# CubePCB.net
KiCad netlist of a schematic drawn in EAGLE
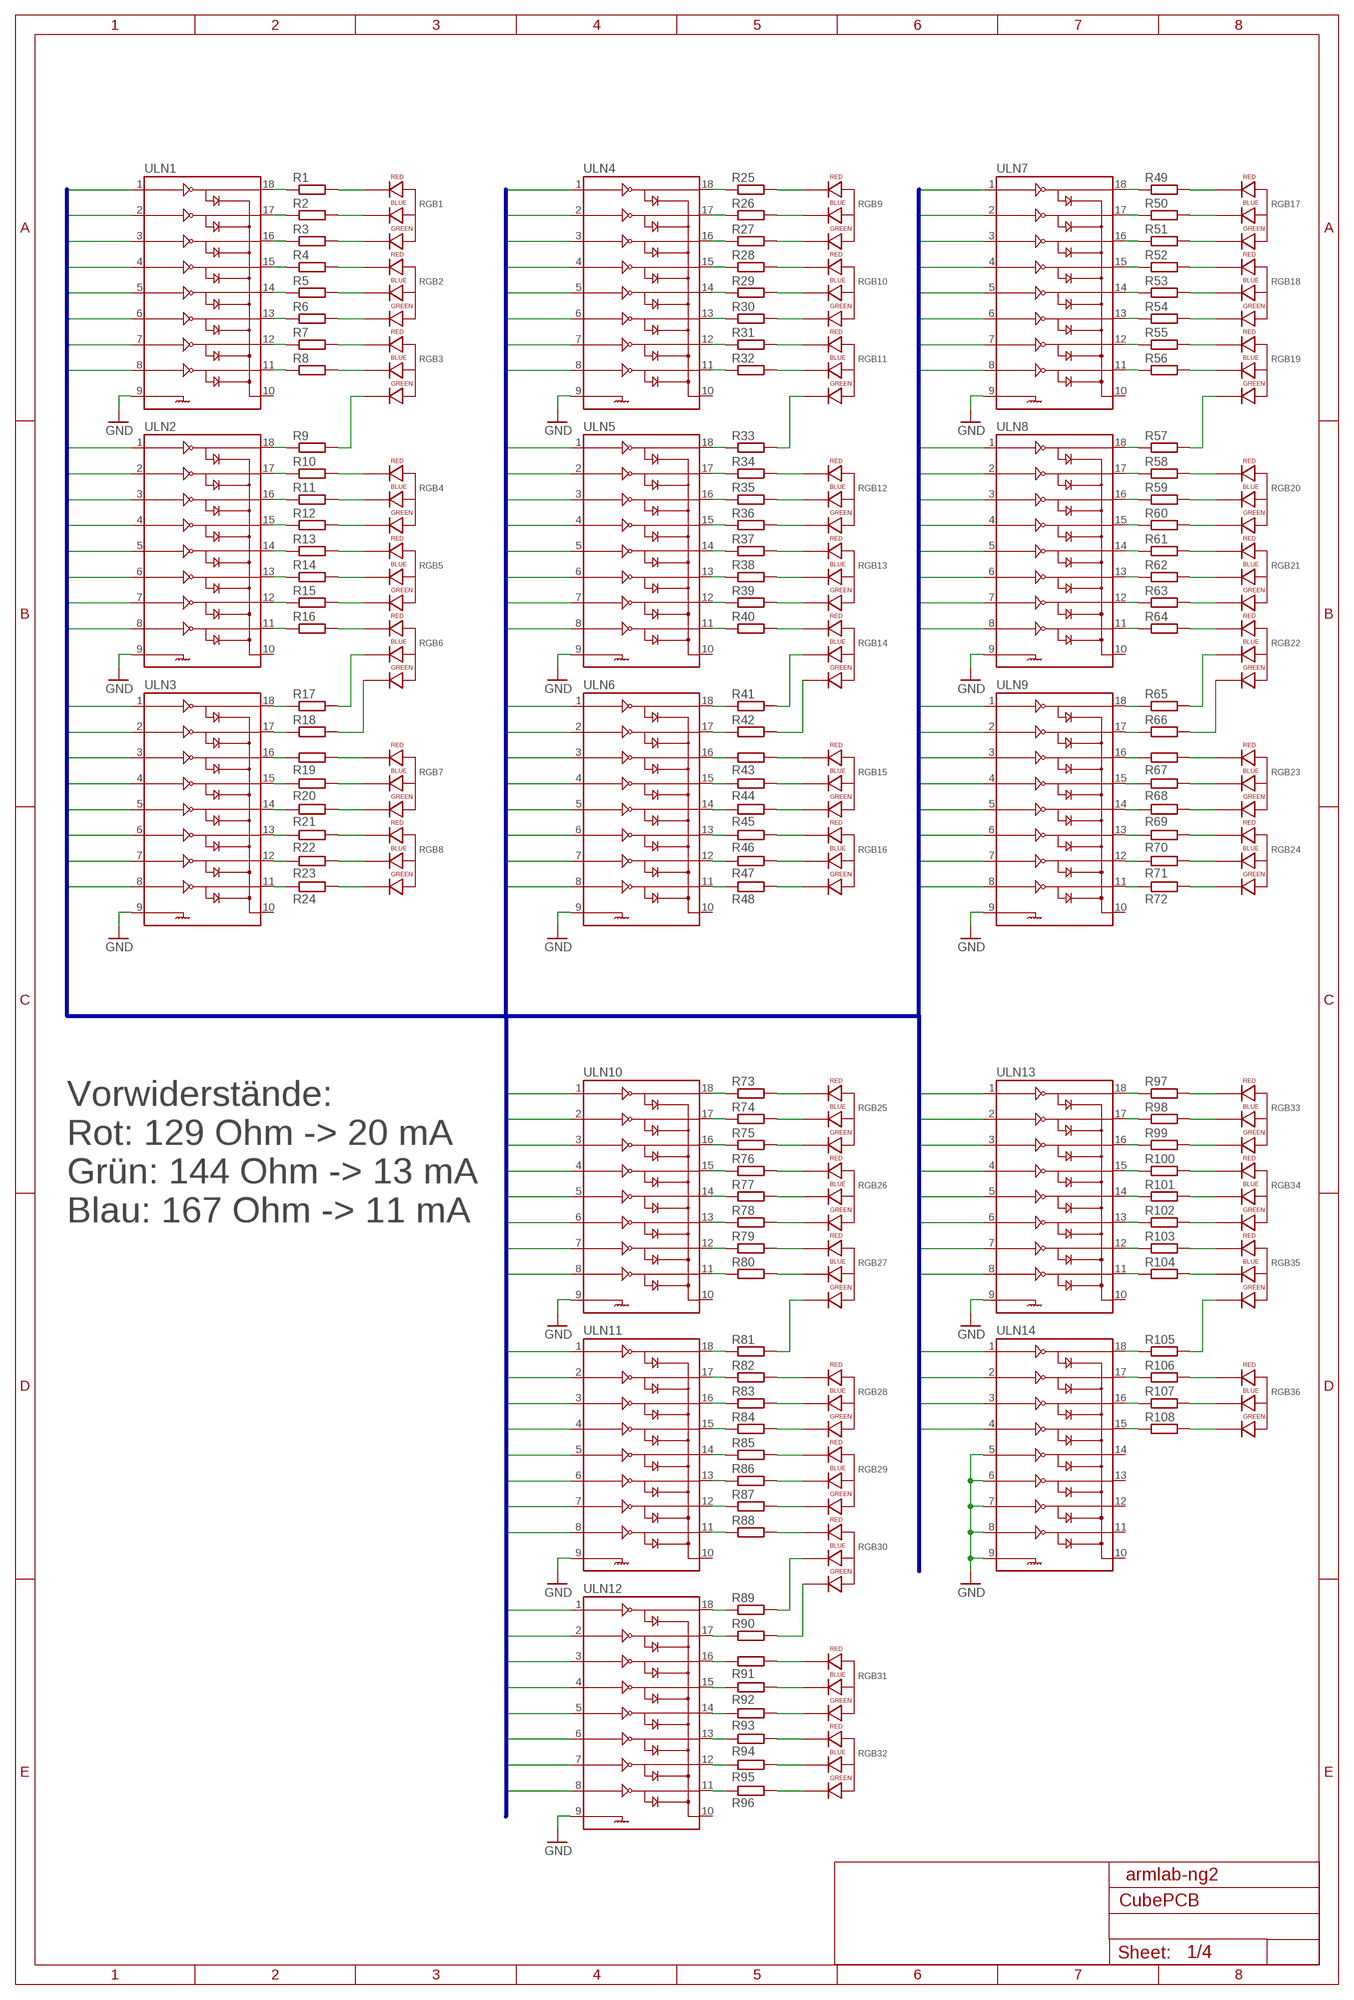
[diagram p0: schematic, sheet 1]
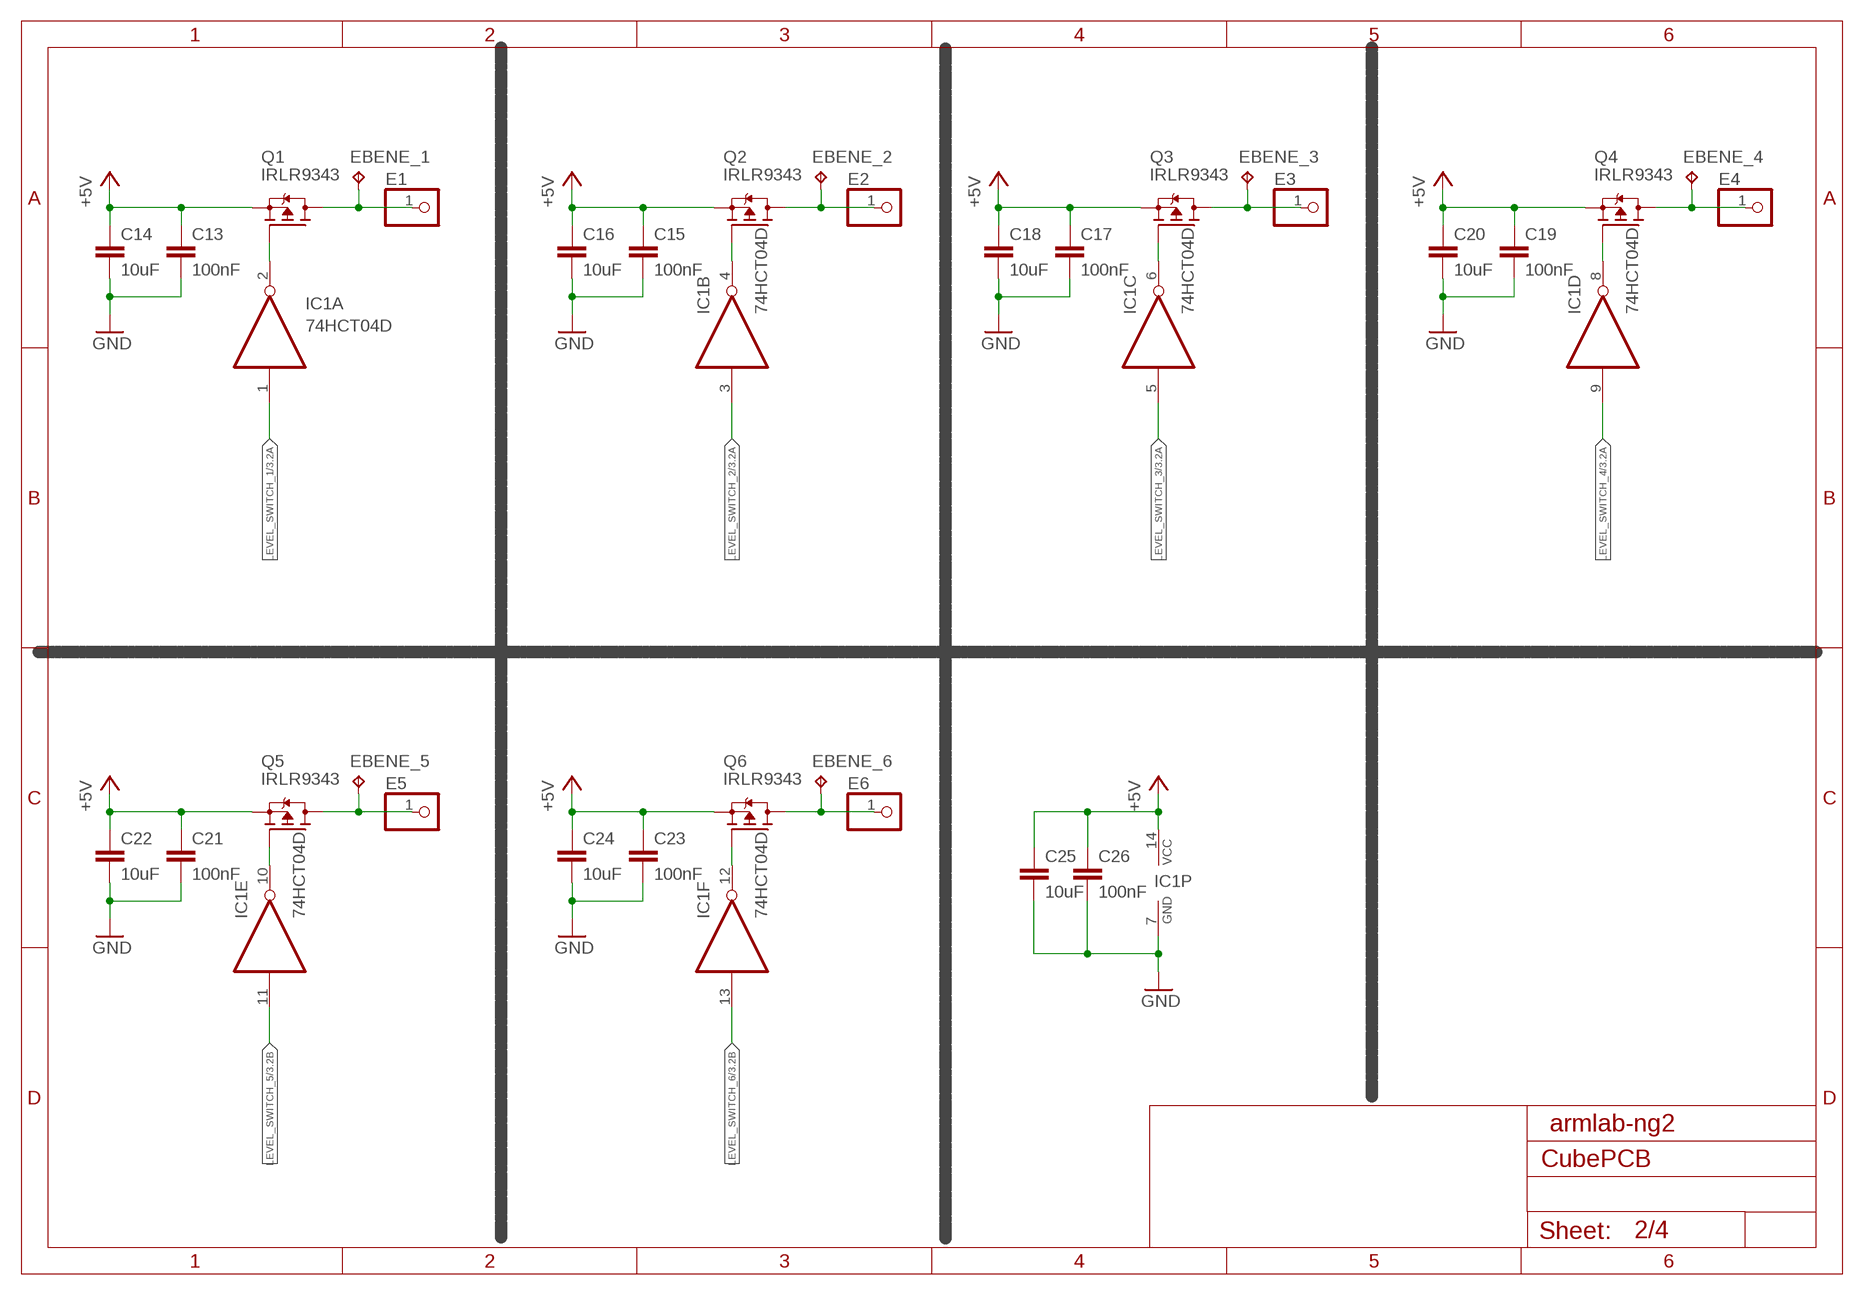
[diagram p1: schematic, sheet 2]
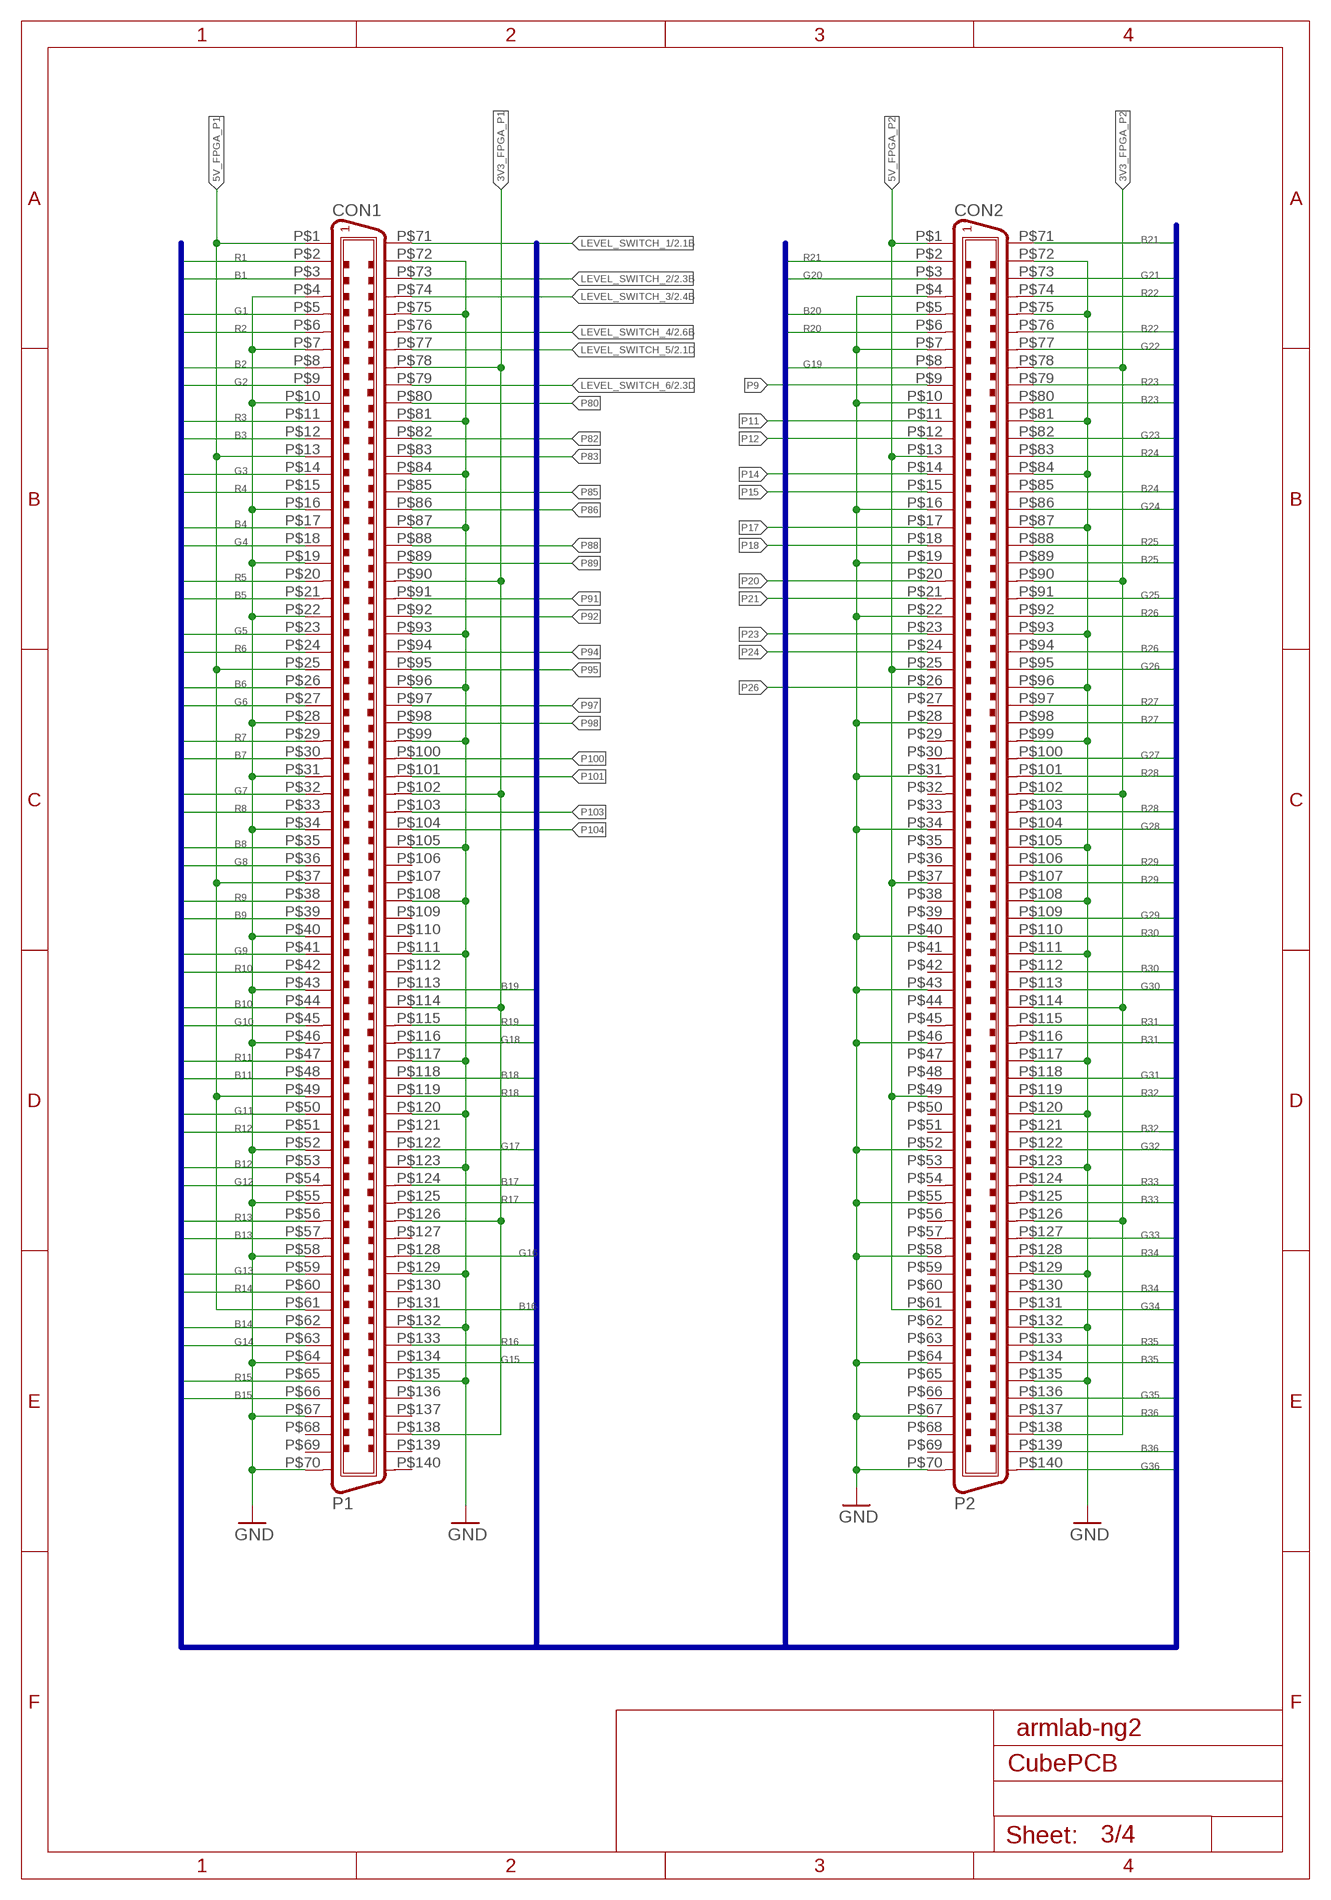
[diagram p2: schematic, sheet 3]
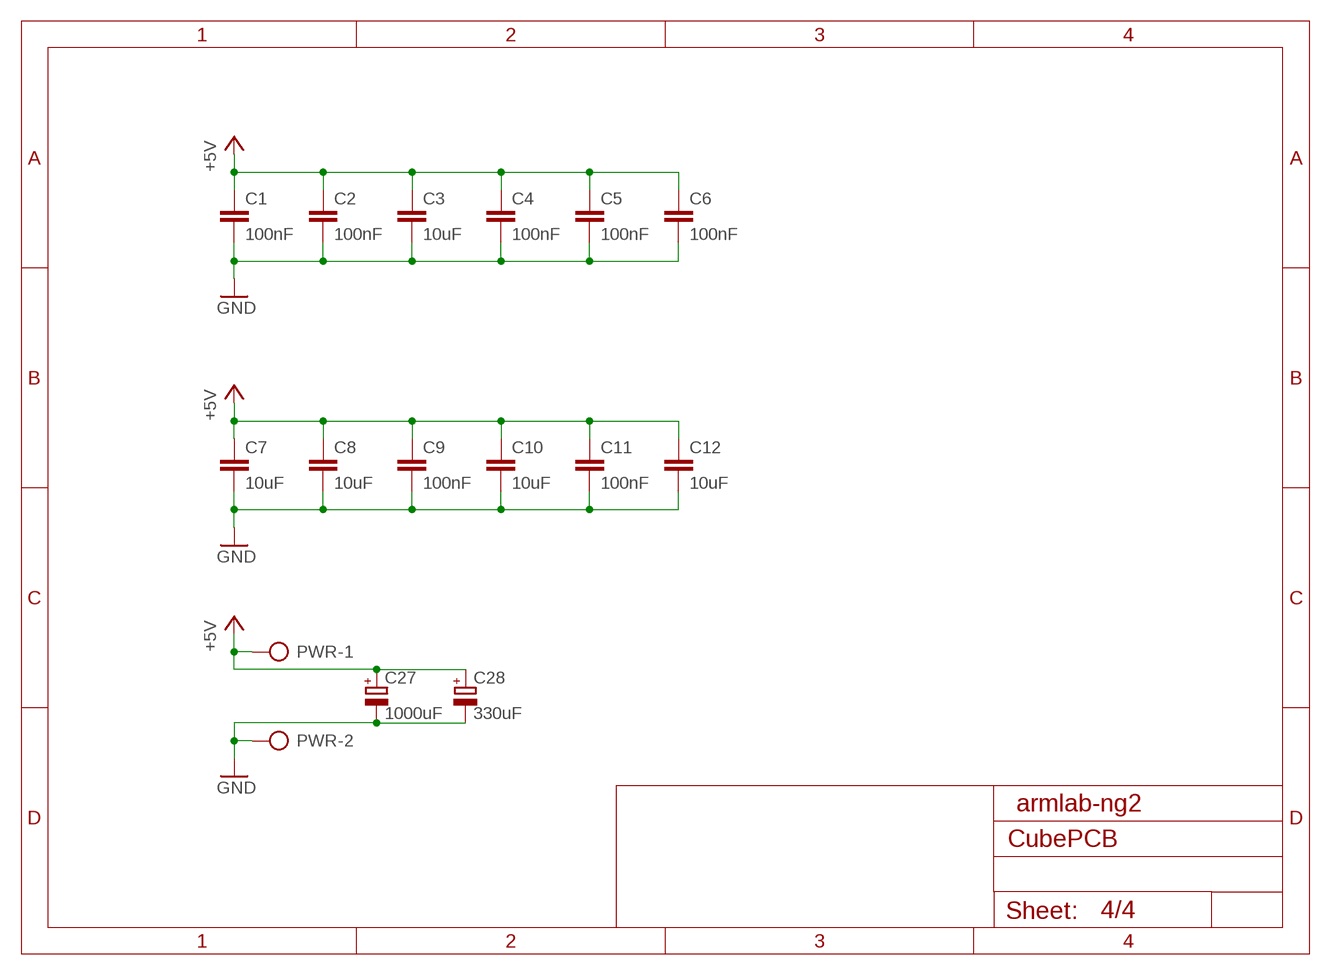
[diagram p3: schematic, sheet 4]

(export (version "E")
  (design (tool "Eeschema 10.0.6"))
  (components
    (comp (ref "C13")
      (value "100nF")
      (footprint "eagle-import:C0603K")
      (libsource (lib "eagle-import") (part "C-EUC0603K"))
    )
    (comp (ref "C14")
      (value "10uF")
      (footprint "eagle-import:C0603K")
      (libsource (lib "eagle-import") (part "C-EUC0603K"))
    )
    (comp (ref "C15")
      (value "100nF")
      (footprint "eagle-import:C0603K")
      (libsource (lib "eagle-import") (part "C-EUC0603K"))
    )
    (comp (ref "C16")
      (value "10uF")
      (footprint "eagle-import:C0603K")
      (libsource (lib "eagle-import") (part "C-EUC0603K"))
    )
    (comp (ref "C17")
      (value "100nF")
      (footprint "eagle-import:C0603K")
      (libsource (lib "eagle-import") (part "C-EUC0603K"))
    )
    (comp (ref "C18")
      (value "10uF")
      (footprint "eagle-import:C0603K")
      (libsource (lib "eagle-import") (part "C-EUC0603K"))
    )
    (comp (ref "C19")
      (value "100nF")
      (footprint "eagle-import:C0603K")
      (libsource (lib "eagle-import") (part "C-EUC0603K"))
    )
    (comp (ref "C20")
      (value "10uF")
      (footprint "eagle-import:C0603K")
      (libsource (lib "eagle-import") (part "C-EUC0603K"))
    )
    (comp (ref "C21")
      (value "100nF")
      (footprint "eagle-import:C0603K")
      (libsource (lib "eagle-import") (part "C-EUC0603K"))
    )
    (comp (ref "C22")
      (value "10uF")
      (footprint "eagle-import:C0603K")
      (libsource (lib "eagle-import") (part "C-EUC0603K"))
    )
    (comp (ref "C23")
      (value "100nF")
      (footprint "eagle-import:C0603K")
      (libsource (lib "eagle-import") (part "C-EUC0603K"))
    )
    (comp (ref "C24")
      (value "10uF")
      (footprint "eagle-import:C0603K")
      (libsource (lib "eagle-import") (part "C-EUC0603K"))
    )
    (comp (ref "C25")
      (value "10uF")
      (footprint "eagle-import:C0603K")
      (libsource (lib "eagle-import") (part "C-EUC0603K"))
    )
    (comp (ref "C26")
      (value "100nF")
      (footprint "eagle-import:C0603K")
      (libsource (lib "eagle-import") (part "C-EUC0603K"))
    )
    (comp (ref "E1")
      (value "PINHD-1X1/LONG")
      (footprint "eagle-import:1X01")
      (libsource (lib "eagle-import") (part "PINHD-1X1/LONG"))
    )
    (comp (ref "E2")
      (value "PINHD-1X1/LONG")
      (footprint "eagle-import:1X01")
      (libsource (lib "eagle-import") (part "PINHD-1X1/LONG"))
    )
    (comp (ref "E3")
      (value "PINHD-1X1/LONG")
      (footprint "eagle-import:1X01")
      (libsource (lib "eagle-import") (part "PINHD-1X1/LONG"))
    )
    (comp (ref "E4")
      (value "PINHD-1X1/LONG")
      (footprint "eagle-import:1X01")
      (libsource (lib "eagle-import") (part "PINHD-1X1/LONG"))
    )
    (comp (ref "E5")
      (value "PINHD-1X1/LONG")
      (footprint "eagle-import:1X01")
      (libsource (lib "eagle-import") (part "PINHD-1X1/LONG"))
    )
    (comp (ref "E6")
      (value "PINHD-1X1/LONG")
      (footprint "eagle-import:1X01")
      (libsource (lib "eagle-import") (part "PINHD-1X1/LONG"))
    )
    (comp (ref "EBENE_1")
      (value "TPB1,27")
      (footprint "eagle-import:B1,27")
      (libsource (lib "eagle-import") (part "TPB1,27"))
    )
    (comp (ref "EBENE_2")
      (value "TPB1,27")
      (footprint "eagle-import:B1,27")
      (libsource (lib "eagle-import") (part "TPB1,27"))
    )
    (comp (ref "EBENE_3")
      (value "TPB1,27")
      (footprint "eagle-import:B1,27")
      (libsource (lib "eagle-import") (part "TPB1,27"))
    )
    (comp (ref "EBENE_4")
      (value "TPB1,27")
      (footprint "eagle-import:B1,27")
      (libsource (lib "eagle-import") (part "TPB1,27"))
    )
    (comp (ref "EBENE_5")
      (value "TPB1,27")
      (footprint "eagle-import:B1,27")
      (libsource (lib "eagle-import") (part "TPB1,27"))
    )
    (comp (ref "EBENE_6")
      (value "TPB1,27")
      (footprint "eagle-import:B1,27")
      (libsource (lib "eagle-import") (part "TPB1,27"))
    )
    (comp (ref "IC1")
      (value "74HCT04D")
      (footprint "eagle-import:SO14")
      (libsource (lib "eagle-import") (part "7404DHCT"))
    )
    (comp (ref "Q1")
      (value "IRLR9343")
      (footprint "eagle-import:TO252")
      (libsource (lib "eagle-import") (part "FDD4141TO252"))
    )
    (comp (ref "Q2")
      (value "IRLR9343")
      (footprint "eagle-import:TO252")
      (libsource (lib "eagle-import") (part "FDD4141TO252"))
    )
    (comp (ref "Q3")
      (value "IRLR9343")
      (footprint "eagle-import:TO252")
      (libsource (lib "eagle-import") (part "FDD4141TO252"))
    )
    (comp (ref "Q4")
      (value "IRLR9343")
      (footprint "eagle-import:TO252")
      (libsource (lib "eagle-import") (part "FDD4141TO252"))
    )
    (comp (ref "Q5")
      (value "IRLR9343")
      (footprint "eagle-import:TO252")
      (libsource (lib "eagle-import") (part "FDD4141TO252"))
    )
    (comp (ref "Q6")
      (value "IRLR9343")
      (footprint "eagle-import:TO252")
      (libsource (lib "eagle-import") (part "FDD4141TO252"))
    )
    (comp (ref "C1")
      (value "100nF")
      (footprint "eagle-import:C0603K")
      (libsource (lib "eagle-import") (part "C-EUC0603K"))
    )
    (comp (ref "C2")
      (value "100nF")
      (footprint "eagle-import:C0603K")
      (libsource (lib "eagle-import") (part "C-EUC0603K"))
    )
    (comp (ref "C3")
      (value "10uF")
      (footprint "eagle-import:C0603K")
      (libsource (lib "eagle-import") (part "C-EUC0603K"))
    )
    (comp (ref "C4")
      (value "100nF")
      (footprint "eagle-import:C0603K")
      (libsource (lib "eagle-import") (part "C-EUC0603K"))
    )
    (comp (ref "C5")
      (value "100nF")
      (footprint "eagle-import:C0603K")
      (libsource (lib "eagle-import") (part "C-EUC0603K"))
    )
    (comp (ref "C6")
      (value "100nF")
      (footprint "eagle-import:C0603K")
      (libsource (lib "eagle-import") (part "C-EUC0603K"))
    )
    (comp (ref "C7")
      (value "10uF")
      (footprint "eagle-import:C0603K")
      (libsource (lib "eagle-import") (part "C-EUC0603K"))
    )
    (comp (ref "C8")
      (value "10uF")
      (footprint "eagle-import:C0603K")
      (libsource (lib "eagle-import") (part "C-EUC0603K"))
    )
    (comp (ref "C9")
      (value "100nF")
      (footprint "eagle-import:C0603K")
      (libsource (lib "eagle-import") (part "C-EUC0603K"))
    )
    (comp (ref "C10")
      (value "10uF")
      (footprint "eagle-import:C0603K")
      (libsource (lib "eagle-import") (part "C-EUC0603K"))
    )
    (comp (ref "C11")
      (value "100nF")
      (footprint "eagle-import:C0603K")
      (libsource (lib "eagle-import") (part "C-EUC0603K"))
    )
    (comp (ref "C12")
      (value "10uF")
      (footprint "eagle-import:C0603K")
      (libsource (lib "eagle-import") (part "C-EUC0603K"))
    )
    (comp (ref "C27")
      (value "1000uF")
      (footprint "eagle-import:E5-10,5")
      (libsource (lib "eagle-import") (part "CPOL-EUE5-10.5"))
    )
    (comp (ref "C28")
      (value "330uF")
      (footprint "eagle-import:E3,5-8")
      (libsource (lib "eagle-import") (part "CPOL-EUE3.5-8"))
    )
    (comp (ref "PWR")
      (value "AK500/2")
      (footprint "eagle-import:AK500_2")
      (libsource (lib "eagle-import") (part "AK500/2"))
    )
    (comp (ref "R1")
      (value "R-EU_R0603")
      (footprint "eagle-import:R0603")
      (libsource (lib "eagle-import") (part "R-EU_R0603"))
    )
    (comp (ref "R2")
      (value "R-EU_R0603")
      (footprint "eagle-import:R0603")
      (libsource (lib "eagle-import") (part "R-EU_R0603"))
    )
    (comp (ref "R3")
      (value "R-EU_R0603")
      (footprint "eagle-import:R0603")
      (libsource (lib "eagle-import") (part "R-EU_R0603"))
    )
    (comp (ref "R4")
      (value "R-EU_R0603")
      (footprint "eagle-import:R0603")
      (libsource (lib "eagle-import") (part "R-EU_R0603"))
    )
    (comp (ref "R5")
      (value "R-EU_R0603")
      (footprint "eagle-import:R0603")
      (libsource (lib "eagle-import") (part "R-EU_R0603"))
    )
    (comp (ref "R6")
      (value "R-EU_R0603")
      (footprint "eagle-import:R0603")
      (libsource (lib "eagle-import") (part "R-EU_R0603"))
    )
    (comp (ref "R7")
      (value "R-EU_R0603")
      (footprint "eagle-import:R0603")
      (libsource (lib "eagle-import") (part "R-EU_R0603"))
    )
    (comp (ref "R8")
      (value "R-EU_R0603")
      (footprint "eagle-import:R0603")
      (libsource (lib "eagle-import") (part "R-EU_R0603"))
    )
    (comp (ref "R9")
      (value "R-EU_R0603")
      (footprint "eagle-import:R0603")
      (libsource (lib "eagle-import") (part "R-EU_R0603"))
    )
    (comp (ref "R10")
      (value "R-EU_R0603")
      (footprint "eagle-import:R0603")
      (libsource (lib "eagle-import") (part "R-EU_R0603"))
    )
    (comp (ref "R11")
      (value "R-EU_R0603")
      (footprint "eagle-import:R0603")
      (libsource (lib "eagle-import") (part "R-EU_R0603"))
    )
    (comp (ref "R12")
      (value "R-EU_R0603")
      (footprint "eagle-import:R0603")
      (libsource (lib "eagle-import") (part "R-EU_R0603"))
    )
    (comp (ref "R13")
      (value "R-EU_R0603")
      (footprint "eagle-import:R0603")
      (libsource (lib "eagle-import") (part "R-EU_R0603"))
    )
    (comp (ref "R14")
      (value "R-EU_R0603")
      (footprint "eagle-import:R0603")
      (libsource (lib "eagle-import") (part "R-EU_R0603"))
    )
    (comp (ref "R15")
      (value "R-EU_R0603")
      (footprint "eagle-import:R0603")
      (libsource (lib "eagle-import") (part "R-EU_R0603"))
    )
    (comp (ref "R16")
      (value "R-EU_R0603")
      (footprint "eagle-import:R0603")
      (libsource (lib "eagle-import") (part "R-EU_R0603"))
    )
    (comp (ref "R17")
      (value "R-EU_R0603")
      (footprint "eagle-import:R0603")
      (libsource (lib "eagle-import") (part "R-EU_R0603"))
    )
    (comp (ref "R18")
      (value "R-EU_R0603")
      (footprint "eagle-import:R0603")
      (libsource (lib "eagle-import") (part "R-EU_R0603"))
    )
    (comp (ref "R19")
      (value "R-EU_R0603")
      (footprint "eagle-import:R0603")
      (libsource (lib "eagle-import") (part "R-EU_R0603"))
    )
    (comp (ref "R20")
      (value "R-EU_R0603")
      (footprint "eagle-import:R0603")
      (libsource (lib "eagle-import") (part "R-EU_R0603"))
    )
    (comp (ref "R21")
      (value "R-EU_R0603")
      (footprint "eagle-import:R0603")
      (libsource (lib "eagle-import") (part "R-EU_R0603"))
    )
    (comp (ref "R22")
      (value "R-EU_R0603")
      (footprint "eagle-import:R0603")
      (libsource (lib "eagle-import") (part "R-EU_R0603"))
    )
    (comp (ref "R23")
      (value "R-EU_R0603")
      (footprint "eagle-import:R0603")
      (libsource (lib "eagle-import") (part "R-EU_R0603"))
    )
    (comp (ref "R24")
      (value "R-EU_R0603")
      (footprint "eagle-import:R0603")
      (libsource (lib "eagle-import") (part "R-EU_R0603"))
    )
    (comp (ref "R25")
      (value "R-EU_R0603")
      (footprint "eagle-import:R0603")
      (libsource (lib "eagle-import") (part "R-EU_R0603"))
    )
    (comp (ref "R26")
      (value "R-EU_R0603")
      (footprint "eagle-import:R0603")
      (libsource (lib "eagle-import") (part "R-EU_R0603"))
    )
    (comp (ref "R27")
      (value "R-EU_R0603")
      (footprint "eagle-import:R0603")
      (libsource (lib "eagle-import") (part "R-EU_R0603"))
    )
    (comp (ref "R28")
      (value "R-EU_R0603")
      (footprint "eagle-import:R0603")
      (libsource (lib "eagle-import") (part "R-EU_R0603"))
    )
    (comp (ref "R29")
      (value "R-EU_R0603")
      (footprint "eagle-import:R0603")
      (libsource (lib "eagle-import") (part "R-EU_R0603"))
    )
    (comp (ref "R30")
      (value "R-EU_R0603")
      (footprint "eagle-import:R0603")
      (libsource (lib "eagle-import") (part "R-EU_R0603"))
    )
    (comp (ref "R31")
      (value "R-EU_R0603")
      (footprint "eagle-import:R0603")
      (libsource (lib "eagle-import") (part "R-EU_R0603"))
    )
    (comp (ref "R32")
      (value "R-EU_R0603")
      (footprint "eagle-import:R0603")
      (libsource (lib "eagle-import") (part "R-EU_R0603"))
    )
    (comp (ref "R33")
      (value "R-EU_R0603")
      (footprint "eagle-import:R0603")
      (libsource (lib "eagle-import") (part "R-EU_R0603"))
    )
    (comp (ref "R34")
      (value "R-EU_R0603")
      (footprint "eagle-import:R0603")
      (libsource (lib "eagle-import") (part "R-EU_R0603"))
    )
    (comp (ref "R35")
      (value "R-EU_R0603")
      (footprint "eagle-import:R0603")
      (libsource (lib "eagle-import") (part "R-EU_R0603"))
    )
    (comp (ref "R36")
      (value "R-EU_R0603")
      (footprint "eagle-import:R0603")
      (libsource (lib "eagle-import") (part "R-EU_R0603"))
    )
    (comp (ref "R37")
      (value "R-EU_R0603")
      (footprint "eagle-import:R0603")
      (libsource (lib "eagle-import") (part "R-EU_R0603"))
    )
    (comp (ref "R38")
      (value "R-EU_R0603")
      (footprint "eagle-import:R0603")
      (libsource (lib "eagle-import") (part "R-EU_R0603"))
    )
    (comp (ref "R39")
      (value "R-EU_R0603")
      (footprint "eagle-import:R0603")
      (libsource (lib "eagle-import") (part "R-EU_R0603"))
    )
    (comp (ref "R40")
      (value "R-EU_R0603")
      (footprint "eagle-import:R0603")
      (libsource (lib "eagle-import") (part "R-EU_R0603"))
    )
    (comp (ref "R41")
      (value "R-EU_R0603")
      (footprint "eagle-import:R0603")
      (libsource (lib "eagle-import") (part "R-EU_R0603"))
    )
    (comp (ref "R42")
      (value "R-EU_R0603")
      (footprint "eagle-import:R0603")
      (libsource (lib "eagle-import") (part "R-EU_R0603"))
    )
    (comp (ref "R43")
      (value "R-EU_R0603")
      (footprint "eagle-import:R0603")
      (libsource (lib "eagle-import") (part "R-EU_R0603"))
    )
    (comp (ref "R44")
      (value "R-EU_R0603")
      (footprint "eagle-import:R0603")
      (libsource (lib "eagle-import") (part "R-EU_R0603"))
    )
    (comp (ref "R45")
      (value "R-EU_R0603")
      (footprint "eagle-import:R0603")
      (libsource (lib "eagle-import") (part "R-EU_R0603"))
    )
    (comp (ref "R46")
      (value "R-EU_R0603")
      (footprint "eagle-import:R0603")
      (libsource (lib "eagle-import") (part "R-EU_R0603"))
    )
    (comp (ref "R47")
      (value "R-EU_R0603")
      (footprint "eagle-import:R0603")
      (libsource (lib "eagle-import") (part "R-EU_R0603"))
    )
    (comp (ref "R48")
      (value "R-EU_R0603")
      (footprint "eagle-import:R0603")
      (libsource (lib "eagle-import") (part "R-EU_R0603"))
    )
    (comp (ref "R49")
      (value "R-EU_R0603")
      (footprint "eagle-import:R0603")
      (libsource (lib "eagle-import") (part "R-EU_R0603"))
    )
    (comp (ref "R50")
      (value "R-EU_R0603")
      (footprint "eagle-import:R0603")
      (libsource (lib "eagle-import") (part "R-EU_R0603"))
    )
    (comp (ref "R51")
      (value "R-EU_R0603")
      (footprint "eagle-import:R0603")
      (libsource (lib "eagle-import") (part "R-EU_R0603"))
    )
    (comp (ref "R52")
      (value "R-EU_R0603")
      (footprint "eagle-import:R0603")
      (libsource (lib "eagle-import") (part "R-EU_R0603"))
    )
    (comp (ref "R53")
      (value "R-EU_R0603")
      (footprint "eagle-import:R0603")
      (libsource (lib "eagle-import") (part "R-EU_R0603"))
    )
    (comp (ref "R54")
      (value "R-EU_R0603")
      (footprint "eagle-import:R0603")
      (libsource (lib "eagle-import") (part "R-EU_R0603"))
    )
    (comp (ref "R55")
      (value "R-EU_R0603")
      (footprint "eagle-import:R0603")
      (libsource (lib "eagle-import") (part "R-EU_R0603"))
    )
    (comp (ref "R56")
      (value "R-EU_R0603")
      (footprint "eagle-import:R0603")
      (libsource (lib "eagle-import") (part "R-EU_R0603"))
    )
    (comp (ref "R57")
      (value "R-EU_R0603")
      (footprint "eagle-import:R0603")
      (libsource (lib "eagle-import") (part "R-EU_R0603"))
    )
    (comp (ref "R58")
      (value "R-EU_R0603")
      (footprint "eagle-import:R0603")
      (libsource (lib "eagle-import") (part "R-EU_R0603"))
    )
    (comp (ref "R59")
      (value "R-EU_R0603")
      (footprint "eagle-import:R0603")
      (libsource (lib "eagle-import") (part "R-EU_R0603"))
    )
    (comp (ref "R60")
      (value "R-EU_R0603")
      (footprint "eagle-import:R0603")
      (libsource (lib "eagle-import") (part "R-EU_R0603"))
    )
    (comp (ref "R61")
      (value "R-EU_R0603")
      (footprint "eagle-import:R0603")
      (libsource (lib "eagle-import") (part "R-EU_R0603"))
    )
    (comp (ref "R62")
      (value "R-EU_R0603")
      (footprint "eagle-import:R0603")
      (libsource (lib "eagle-import") (part "R-EU_R0603"))
    )
    (comp (ref "R63")
      (value "R-EU_R0603")
      (footprint "eagle-import:R0603")
      (libsource (lib "eagle-import") (part "R-EU_R0603"))
    )
    (comp (ref "R64")
      (value "R-EU_R0603")
      (footprint "eagle-import:R0603")
      (libsource (lib "eagle-import") (part "R-EU_R0603"))
    )
    (comp (ref "R65")
      (value "R-EU_R0603")
      (footprint "eagle-import:R0603")
      (libsource (lib "eagle-import") (part "R-EU_R0603"))
    )
    (comp (ref "R66")
      (value "R-EU_R0603")
      (footprint "eagle-import:R0603")
      (libsource (lib "eagle-import") (part "R-EU_R0603"))
    )
    (comp (ref "R67")
      (value "R-EU_R0603")
      (footprint "eagle-import:R0603")
      (libsource (lib "eagle-import") (part "R-EU_R0603"))
    )
    (comp (ref "R68")
      (value "R-EU_R0603")
      (footprint "eagle-import:R0603")
      (libsource (lib "eagle-import") (part "R-EU_R0603"))
    )
    (comp (ref "R69")
      (value "R-EU_R0603")
      (footprint "eagle-import:R0603")
      (libsource (lib "eagle-import") (part "R-EU_R0603"))
    )
    (comp (ref "R70")
      (value "R-EU_R0603")
      (footprint "eagle-import:R0603")
      (libsource (lib "eagle-import") (part "R-EU_R0603"))
    )
    (comp (ref "R71")
      (value "R-EU_R0603")
      (footprint "eagle-import:R0603")
      (libsource (lib "eagle-import") (part "R-EU_R0603"))
    )
    (comp (ref "R72")
      (value "R-EU_R0603")
      (footprint "eagle-import:R0603")
      (libsource (lib "eagle-import") (part "R-EU_R0603"))
    )
    (comp (ref "R73")
      (value "R-EU_R0603")
      (footprint "eagle-import:R0603")
      (libsource (lib "eagle-import") (part "R-EU_R0603"))
    )
    (comp (ref "R74")
      (value "R-EU_R0603")
      (footprint "eagle-import:R0603")
      (libsource (lib "eagle-import") (part "R-EU_R0603"))
    )
    (comp (ref "R75")
      (value "R-EU_R0603")
      (footprint "eagle-import:R0603")
      (libsource (lib "eagle-import") (part "R-EU_R0603"))
    )
    (comp (ref "R76")
      (value "R-EU_R0603")
      (footprint "eagle-import:R0603")
      (libsource (lib "eagle-import") (part "R-EU_R0603"))
    )
    (comp (ref "R77")
      (value "R-EU_R0603")
      (footprint "eagle-import:R0603")
      (libsource (lib "eagle-import") (part "R-EU_R0603"))
    )
    (comp (ref "R78")
      (value "R-EU_R0603")
      (footprint "eagle-import:R0603")
      (libsource (lib "eagle-import") (part "R-EU_R0603"))
    )
    (comp (ref "R79")
      (value "R-EU_R0603")
      (footprint "eagle-import:R0603")
      (libsource (lib "eagle-import") (part "R-EU_R0603"))
    )
    (comp (ref "R80")
      (value "R-EU_R0603")
      (footprint "eagle-import:R0603")
      (libsource (lib "eagle-import") (part "R-EU_R0603"))
    )
    (comp (ref "R81")
      (value "R-EU_R0603")
      (footprint "eagle-import:R0603")
      (libsource (lib "eagle-import") (part "R-EU_R0603"))
    )
    (comp (ref "R82")
      (value "R-EU_R0603")
      (footprint "eagle-import:R0603")
      (libsource (lib "eagle-import") (part "R-EU_R0603"))
    )
    (comp (ref "R83")
      (value "R-EU_R0603")
      (footprint "eagle-import:R0603")
      (libsource (lib "eagle-import") (part "R-EU_R0603"))
    )
    (comp (ref "R84")
      (value "R-EU_R0603")
      (footprint "eagle-import:R0603")
      (libsource (lib "eagle-import") (part "R-EU_R0603"))
    )
    (comp (ref "R85")
      (value "R-EU_R0603")
      (footprint "eagle-import:R0603")
      (libsource (lib "eagle-import") (part "R-EU_R0603"))
    )
    (comp (ref "R86")
      (value "R-EU_R0603")
      (footprint "eagle-import:R0603")
      (libsource (lib "eagle-import") (part "R-EU_R0603"))
    )
    (comp (ref "R87")
      (value "R-EU_R0603")
      (footprint "eagle-import:R0603")
      (libsource (lib "eagle-import") (part "R-EU_R0603"))
    )
    (comp (ref "R88")
      (value "R-EU_R0603")
      (footprint "eagle-import:R0603")
      (libsource (lib "eagle-import") (part "R-EU_R0603"))
    )
    (comp (ref "R89")
      (value "R-EU_R0603")
      (footprint "eagle-import:R0603")
      (libsource (lib "eagle-import") (part "R-EU_R0603"))
    )
    (comp (ref "R90")
      (value "R-EU_R0603")
      (footprint "eagle-import:R0603")
      (libsource (lib "eagle-import") (part "R-EU_R0603"))
    )
    (comp (ref "R91")
      (value "R-EU_R0603")
      (footprint "eagle-import:R0603")
      (libsource (lib "eagle-import") (part "R-EU_R0603"))
    )
    (comp (ref "R92")
      (value "R-EU_R0603")
      (footprint "eagle-import:R0603")
      (libsource (lib "eagle-import") (part "R-EU_R0603"))
    )
    (comp (ref "R93")
      (value "R-EU_R0603")
      (footprint "eagle-import:R0603")
      (libsource (lib "eagle-import") (part "R-EU_R0603"))
    )
    (comp (ref "R94")
      (value "R-EU_R0603")
      (footprint "eagle-import:R0603")
      (libsource (lib "eagle-import") (part "R-EU_R0603"))
    )
    (comp (ref "R95")
      (value "R-EU_R0603")
      (footprint "eagle-import:R0603")
      (libsource (lib "eagle-import") (part "R-EU_R0603"))
    )
    (comp (ref "R96")
      (value "R-EU_R0603")
      (footprint "eagle-import:R0603")
      (libsource (lib "eagle-import") (part "R-EU_R0603"))
    )
    (comp (ref "R97")
      (value "R-EU_R0603")
      (footprint "eagle-import:R0603")
      (libsource (lib "eagle-import") (part "R-EU_R0603"))
    )
    (comp (ref "R98")
      (value "R-EU_R0603")
      (footprint "eagle-import:R0603")
      (libsource (lib "eagle-import") (part "R-EU_R0603"))
    )
    (comp (ref "R99")
      (value "R-EU_R0603")
      (footprint "eagle-import:R0603")
      (libsource (lib "eagle-import") (part "R-EU_R0603"))
    )
    (comp (ref "R100")
      (value "R-EU_R0603")
      (footprint "eagle-import:R0603")
      (libsource (lib "eagle-import") (part "R-EU_R0603"))
    )
    (comp (ref "R101")
      (value "R-EU_R0603")
      (footprint "eagle-import:R0603")
      (libsource (lib "eagle-import") (part "R-EU_R0603"))
    )
    (comp (ref "R102")
      (value "R-EU_R0603")
      (footprint "eagle-import:R0603")
      (libsource (lib "eagle-import") (part "R-EU_R0603"))
    )
    (comp (ref "R103")
      (value "R-EU_R0603")
      (footprint "eagle-import:R0603")
      (libsource (lib "eagle-import") (part "R-EU_R0603"))
    )
    (comp (ref "R104")
      (value "R-EU_R0603")
      (footprint "eagle-import:R0603")
      (libsource (lib "eagle-import") (part "R-EU_R0603"))
    )
    (comp (ref "R105")
      (value "R-EU_R0603")
      (footprint "eagle-import:R0603")
      (libsource (lib "eagle-import") (part "R-EU_R0603"))
    )
    (comp (ref "R106")
      (value "R-EU_R0603")
      (footprint "eagle-import:R0603")
      (libsource (lib "eagle-import") (part "R-EU_R0603"))
    )
    (comp (ref "R107")
      (value "R-EU_R0603")
      (footprint "eagle-import:R0603")
      (libsource (lib "eagle-import") (part "R-EU_R0603"))
    )
    (comp (ref "R108")
      (value "R-EU_R0603")
      (footprint "eagle-import:R0603")
      (libsource (lib "eagle-import") (part "R-EU_R0603"))
    )
    (comp (ref "RGB1")
      (value "LED-RGB-CA-ANODE-SPLIT")
      (footprint "eagle-import:LED-RGB-WO-ANODE")
      (libsource (lib "eagle-import") (part "LED-RGB-CA-ANODE-SPLIT"))
    )
    (comp (ref "RGB2")
      (value "LED-RGB-CA-ANODE-SPLIT")
      (footprint "eagle-import:LED-RGB-WO-ANODE")
      (libsource (lib "eagle-import") (part "LED-RGB-CA-ANODE-SPLIT"))
    )
    (comp (ref "RGB3")
      (value "LED-RGB-CA-ANODE-SPLIT")
      (footprint "eagle-import:LED-RGB-WO-ANODE")
      (libsource (lib "eagle-import") (part "LED-RGB-CA-ANODE-SPLIT"))
    )
    (comp (ref "RGB4")
      (value "LED-RGB-CA-ANODE-SPLIT")
      (footprint "eagle-import:LED-RGB-WO-ANODE")
      (libsource (lib "eagle-import") (part "LED-RGB-CA-ANODE-SPLIT"))
    )
    (comp (ref "RGB5")
      (value "LED-RGB-CA-ANODE-SPLIT")
      (footprint "eagle-import:LED-RGB-WO-ANODE")
      (libsource (lib "eagle-import") (part "LED-RGB-CA-ANODE-SPLIT"))
    )
    (comp (ref "RGB6")
      (value "LED-RGB-CA-ANODE-SPLIT")
      (footprint "eagle-import:LED-RGB-WO-ANODE")
      (libsource (lib "eagle-import") (part "LED-RGB-CA-ANODE-SPLIT"))
    )
    (comp (ref "RGB7")
      (value "LED-RGB-CA-ANODE-SPLIT")
      (footprint "eagle-import:LED-RGB-WO-ANODE")
      (libsource (lib "eagle-import") (part "LED-RGB-CA-ANODE-SPLIT"))
    )
    (comp (ref "RGB8")
      (value "LED-RGB-CA-ANODE-SPLIT")
      (footprint "eagle-import:LED-RGB-WO-ANODE")
      (libsource (lib "eagle-import") (part "LED-RGB-CA-ANODE-SPLIT"))
    )
    (comp (ref "RGB9")
      (value "LED-RGB-CA-ANODE-SPLIT")
      (footprint "eagle-import:LED-RGB-WO-ANODE")
      (libsource (lib "eagle-import") (part "LED-RGB-CA-ANODE-SPLIT"))
    )
    (comp (ref "RGB10")
      (value "LED-RGB-CA-ANODE-SPLIT")
      (footprint "eagle-import:LED-RGB-WO-ANODE")
      (libsource (lib "eagle-import") (part "LED-RGB-CA-ANODE-SPLIT"))
    )
    (comp (ref "RGB11")
      (value "LED-RGB-CA-ANODE-SPLIT")
      (footprint "eagle-import:LED-RGB-WO-ANODE")
      (libsource (lib "eagle-import") (part "LED-RGB-CA-ANODE-SPLIT"))
    )
    (comp (ref "RGB12")
      (value "LED-RGB-CA-ANODE-SPLIT")
      (footprint "eagle-import:LED-RGB-WO-ANODE")
      (libsource (lib "eagle-import") (part "LED-RGB-CA-ANODE-SPLIT"))
    )
    (comp (ref "RGB13")
      (value "LED-RGB-CA-ANODE-SPLIT")
      (footprint "eagle-import:LED-RGB-WO-ANODE")
      (libsource (lib "eagle-import") (part "LED-RGB-CA-ANODE-SPLIT"))
    )
    (comp (ref "RGB14")
      (value "LED-RGB-CA-ANODE-SPLIT")
      (footprint "eagle-import:LED-RGB-WO-ANODE")
      (libsource (lib "eagle-import") (part "LED-RGB-CA-ANODE-SPLIT"))
    )
    (comp (ref "RGB15")
      (value "LED-RGB-CA-ANODE-SPLIT")
      (footprint "eagle-import:LED-RGB-WO-ANODE")
      (libsource (lib "eagle-import") (part "LED-RGB-CA-ANODE-SPLIT"))
    )
    (comp (ref "RGB16")
      (value "LED-RGB-CA-ANODE-SPLIT")
      (footprint "eagle-import:LED-RGB-WO-ANODE")
      (libsource (lib "eagle-import") (part "LED-RGB-CA-ANODE-SPLIT"))
    )
    (comp (ref "RGB17")
      (value "LED-RGB-CA-ANODE-SPLIT")
      (footprint "eagle-import:LED-RGB-WO-ANODE")
      (libsource (lib "eagle-import") (part "LED-RGB-CA-ANODE-SPLIT"))
    )
    (comp (ref "RGB18")
      (value "LED-RGB-CA-ANODE-SPLIT")
      (footprint "eagle-import:LED-RGB-WO-ANODE")
      (libsource (lib "eagle-import") (part "LED-RGB-CA-ANODE-SPLIT"))
    )
    (comp (ref "RGB19")
      (value "LED-RGB-CA-ANODE-SPLIT")
      (footprint "eagle-import:LED-RGB-WO-ANODE")
      (libsource (lib "eagle-import") (part "LED-RGB-CA-ANODE-SPLIT"))
    )
    (comp (ref "RGB20")
      (value "LED-RGB-CA-ANODE-SPLIT")
      (footprint "eagle-import:LED-RGB-WO-ANODE")
      (libsource (lib "eagle-import") (part "LED-RGB-CA-ANODE-SPLIT"))
    )
    (comp (ref "RGB21")
      (value "LED-RGB-CA-ANODE-SPLIT")
      (footprint "eagle-import:LED-RGB-WO-ANODE")
      (libsource (lib "eagle-import") (part "LED-RGB-CA-ANODE-SPLIT"))
    )
    (comp (ref "RGB22")
      (value "LED-RGB-CA-ANODE-SPLIT")
      (footprint "eagle-import:LED-RGB-WO-ANODE")
      (libsource (lib "eagle-import") (part "LED-RGB-CA-ANODE-SPLIT"))
    )
    (comp (ref "RGB23")
      (value "LED-RGB-CA-ANODE-SPLIT")
      (footprint "eagle-import:LED-RGB-WO-ANODE")
      (libsource (lib "eagle-import") (part "LED-RGB-CA-ANODE-SPLIT"))
    )
    (comp (ref "RGB24")
      (value "LED-RGB-CA-ANODE-SPLIT")
      (footprint "eagle-import:LED-RGB-WO-ANODE")
      (libsource (lib "eagle-import") (part "LED-RGB-CA-ANODE-SPLIT"))
    )
    (comp (ref "RGB25")
      (value "LED-RGB-CA-ANODE-SPLIT")
      (footprint "eagle-import:LED-RGB-WO-ANODE")
      (libsource (lib "eagle-import") (part "LED-RGB-CA-ANODE-SPLIT"))
    )
    (comp (ref "RGB26")
      (value "LED-RGB-CA-ANODE-SPLIT")
      (footprint "eagle-import:LED-RGB-WO-ANODE")
      (libsource (lib "eagle-import") (part "LED-RGB-CA-ANODE-SPLIT"))
    )
    (comp (ref "RGB27")
      (value "LED-RGB-CA-ANODE-SPLIT")
      (footprint "eagle-import:LED-RGB-WO-ANODE")
      (libsource (lib "eagle-import") (part "LED-RGB-CA-ANODE-SPLIT"))
    )
    (comp (ref "RGB28")
      (value "LED-RGB-CA-ANODE-SPLIT")
      (footprint "eagle-import:LED-RGB-WO-ANODE")
      (libsource (lib "eagle-import") (part "LED-RGB-CA-ANODE-SPLIT"))
    )
    (comp (ref "RGB29")
      (value "LED-RGB-CA-ANODE-SPLIT")
      (footprint "eagle-import:LED-RGB-WO-ANODE")
      (libsource (lib "eagle-import") (part "LED-RGB-CA-ANODE-SPLIT"))
    )
    (comp (ref "RGB30")
      (value "LED-RGB-CA-ANODE-SPLIT")
      (footprint "eagle-import:LED-RGB-WO-ANODE")
      (libsource (lib "eagle-import") (part "LED-RGB-CA-ANODE-SPLIT"))
    )
    (comp (ref "RGB31")
      (value "LED-RGB-CA-ANODE-SPLIT")
      (footprint "eagle-import:LED-RGB-WO-ANODE")
      (libsource (lib "eagle-import") (part "LED-RGB-CA-ANODE-SPLIT"))
    )
    (comp (ref "RGB32")
      (value "LED-RGB-CA-ANODE-SPLIT")
      (footprint "eagle-import:LED-RGB-WO-ANODE")
      (libsource (lib "eagle-import") (part "LED-RGB-CA-ANODE-SPLIT"))
    )
    (comp (ref "RGB33")
      (value "LED-RGB-CA-ANODE-SPLIT")
      (footprint "eagle-import:LED-RGB-WO-ANODE")
      (libsource (lib "eagle-import") (part "LED-RGB-CA-ANODE-SPLIT"))
    )
    (comp (ref "RGB34")
      (value "LED-RGB-CA-ANODE-SPLIT")
      (footprint "eagle-import:LED-RGB-WO-ANODE")
      (libsource (lib "eagle-import") (part "LED-RGB-CA-ANODE-SPLIT"))
    )
    (comp (ref "RGB35")
      (value "LED-RGB-CA-ANODE-SPLIT")
      (footprint "eagle-import:LED-RGB-WO-ANODE")
      (libsource (lib "eagle-import") (part "LED-RGB-CA-ANODE-SPLIT"))
    )
    (comp (ref "RGB36")
      (value "LED-RGB-CA-ANODE-SPLIT")
      (footprint "eagle-import:LED-RGB-WO-ANODE")
      (libsource (lib "eagle-import") (part "LED-RGB-CA-ANODE-SPLIT"))
    )
    (comp (ref "ULN1")
      (value "ULN2803SOICW")
      (footprint "eagle-import:SO18L")
      (libsource (lib "eagle-import") (part "ULN2803SOICW"))
    )
    (comp (ref "ULN2")
      (value "ULN2803SOICW")
      (footprint "eagle-import:SO18L")
      (libsource (lib "eagle-import") (part "ULN2803SOICW"))
    )
    (comp (ref "ULN3")
      (value "ULN2803SOICW")
      (footprint "eagle-import:SO18L")
      (libsource (lib "eagle-import") (part "ULN2803SOICW"))
    )
    (comp (ref "ULN4")
      (value "ULN2803SOICW")
      (footprint "eagle-import:SO18L")
      (libsource (lib "eagle-import") (part "ULN2803SOICW"))
    )
    (comp (ref "ULN5")
      (value "ULN2803SOICW")
      (footprint "eagle-import:SO18L")
      (libsource (lib "eagle-import") (part "ULN2803SOICW"))
    )
    (comp (ref "ULN6")
      (value "ULN2803SOICW")
      (footprint "eagle-import:SO18L")
      (libsource (lib "eagle-import") (part "ULN2803SOICW"))
    )
    (comp (ref "ULN7")
      (value "ULN2803SOICW")
      (footprint "eagle-import:SO18L")
      (libsource (lib "eagle-import") (part "ULN2803SOICW"))
    )
    (comp (ref "ULN8")
      (value "ULN2803SOICW")
      (footprint "eagle-import:SO18L")
      (libsource (lib "eagle-import") (part "ULN2803SOICW"))
    )
    (comp (ref "ULN9")
      (value "ULN2803SOICW")
      (footprint "eagle-import:SO18L")
      (libsource (lib "eagle-import") (part "ULN2803SOICW"))
    )
    (comp (ref "ULN10")
      (value "ULN2803SOICW")
      (footprint "eagle-import:SO18L")
      (libsource (lib "eagle-import") (part "ULN2803SOICW"))
    )
    (comp (ref "ULN11")
      (value "ULN2803SOICW")
      (footprint "eagle-import:SO18L")
      (libsource (lib "eagle-import") (part "ULN2803SOICW"))
    )
    (comp (ref "ULN12")
      (value "ULN2803SOICW")
      (footprint "eagle-import:SO18L")
      (libsource (lib "eagle-import") (part "ULN2803SOICW"))
    )
    (comp (ref "ULN13")
      (value "ULN2803SOICW")
      (footprint "eagle-import:SO18L")
      (libsource (lib "eagle-import") (part "ULN2803SOICW"))
    )
    (comp (ref "ULN14")
      (value "ULN2803SOICW")
      (footprint "eagle-import:SO18L")
      (libsource (lib "eagle-import") (part "ULN2803SOICW"))
    )
    (comp (ref "CON1")
      (value "P1")
      (footprint "eagle-import:140-FH0.8")
      (libsource (lib "eagle-import") (part "AVBUS_CONNECTOR_140-2"))
    )
    (comp (ref "CON2")
      (value "P2")
      (footprint "eagle-import:140-FH0.8")
      (libsource (lib "eagle-import") (part "AVBUS_CONNECTOR_140-2"))
    )
  )
  (nets
    (net (code "1") (name "+5V") (class "Default")
      (node (ref "C1") (pin "1") (pinfunction "1_1") (pintype "passive"))
      (node (ref "C10") (pin "1") (pinfunction "1_1") (pintype "passive"))
      (node (ref "C11") (pin "1") (pinfunction "1_1") (pintype "passive"))
      (node (ref "C12") (pin "1") (pinfunction "1_1") (pintype "passive"))
      (node (ref "C13") (pin "1") (pinfunction "1_1") (pintype "passive"))
      (node (ref "C14") (pin "1") (pinfunction "1_1") (pintype "passive"))
      (node (ref "C15") (pin "1") (pinfunction "1_1") (pintype "passive"))
      (node (ref "C16") (pin "1") (pinfunction "1_1") (pintype "passive"))
      (node (ref "C17") (pin "1") (pinfunction "1_1") (pintype "passive"))
      (node (ref "C18") (pin "1") (pinfunction "1_1") (pintype "passive"))
      (node (ref "C19") (pin "1") (pinfunction "1_1") (pintype "passive"))
      (node (ref "C2") (pin "1") (pinfunction "1_1") (pintype "passive"))
      (node (ref "C20") (pin "1") (pinfunction "1_1") (pintype "passive"))
      (node (ref "C21") (pin "1") (pinfunction "1_1") (pintype "passive"))
      (node (ref "C22") (pin "1") (pinfunction "1_1") (pintype "passive"))
      (node (ref "C23") (pin "1") (pinfunction "1_1") (pintype "passive"))
      (node (ref "C24") (pin "1") (pinfunction "1_1") (pintype "passive"))
      (node (ref "C25") (pin "1") (pinfunction "1_1") (pintype "passive"))
      (node (ref "C26") (pin "1") (pinfunction "1_1") (pintype "passive"))
      (node (ref "C27") (pin "+") (pinfunction "+_+") (pintype "passive"))
      (node (ref "C28") (pin "+") (pinfunction "+_+") (pintype "passive"))
      (node (ref "C3") (pin "1") (pinfunction "1_1") (pintype "passive"))
      (node (ref "C4") (pin "1") (pinfunction "1_1") (pintype "passive"))
      (node (ref "C5") (pin "1") (pinfunction "1_1") (pintype "passive"))
      (node (ref "C6") (pin "1") (pinfunction "1_1") (pintype "passive"))
      (node (ref "C7") (pin "1") (pinfunction "1_1") (pintype "passive"))
      (node (ref "C8") (pin "1") (pinfunction "1_1") (pintype "passive"))
      (node (ref "C9") (pin "1") (pinfunction "1_1") (pintype "passive"))
      (node (ref "IC1") (pin "14") (pinfunction "VCC_14") (pintype "power_in"))
      (node (ref "PWR") (pin "1") (pinfunction "KL_1") (pintype "passive"))
      (node (ref "Q1") (pin "2") (pinfunction "S_2") (pintype "passive"))
      (node (ref "Q2") (pin "2") (pinfunction "S_2") (pintype "passive"))
      (node (ref "Q3") (pin "2") (pinfunction "S_2") (pintype "passive"))
      (node (ref "Q4") (pin "2") (pinfunction "S_2") (pintype "passive"))
      (node (ref "Q5") (pin "2") (pinfunction "S_2") (pintype "passive"))
      (node (ref "Q6") (pin "2") (pinfunction "S_2") (pintype "passive"))
    )
    (net (code "2") (name "3V3_FPGA_P1") (class "Default")
      (node (ref "CON1") (pin "P$102") (pinfunction "102_P$102") (pintype "passive"))
      (node (ref "CON1") (pin "P$114") (pinfunction "114_P$114") (pintype "passive"))
      (node (ref "CON1") (pin "P$126") (pinfunction "126_P$126") (pintype "passive"))
      (node (ref "CON1") (pin "P$138") (pinfunction "138_P$138") (pintype "passive"))
      (node (ref "CON1") (pin "P$78") (pinfunction "78_P$78") (pintype "passive"))
      (node (ref "CON1") (pin "P$90") (pinfunction "90_P$90") (pintype "passive"))
    )
    (net (code "3") (name "3V3_FPGA_P2") (class "Default")
      (node (ref "CON2") (pin "P$102") (pinfunction "102_P$102") (pintype "passive"))
      (node (ref "CON2") (pin "P$114") (pinfunction "114_P$114") (pintype "passive"))
      (node (ref "CON2") (pin "P$126") (pinfunction "126_P$126") (pintype "passive"))
      (node (ref "CON2") (pin "P$138") (pinfunction "138_P$138") (pintype "passive"))
      (node (ref "CON2") (pin "P$78") (pinfunction "78_P$78") (pintype "passive"))
      (node (ref "CON2") (pin "P$90") (pinfunction "90_P$90") (pintype "passive"))
    )
    (net (code "4") (name "5V_FPGA_P1") (class "Default")
      (node (ref "CON1") (pin "P$1") (pinfunction "1_P$1") (pintype "passive"))
      (node (ref "CON1") (pin "P$13") (pinfunction "13_P$13") (pintype "passive"))
      (node (ref "CON1") (pin "P$25") (pinfunction "25_P$25") (pintype "passive"))
      (node (ref "CON1") (pin "P$37") (pinfunction "37_P$37") (pintype "passive"))
      (node (ref "CON1") (pin "P$49") (pinfunction "49_P$49") (pintype "passive"))
      (node (ref "CON1") (pin "P$61") (pinfunction "61_P$61") (pintype "passive"))
    )
    (net (code "5") (name "5V_FPGA_P2") (class "Default")
      (node (ref "CON2") (pin "P$1") (pinfunction "1_P$1") (pintype "passive"))
      (node (ref "CON2") (pin "P$13") (pinfunction "13_P$13") (pintype "passive"))
      (node (ref "CON2") (pin "P$25") (pinfunction "25_P$25") (pintype "passive"))
      (node (ref "CON2") (pin "P$37") (pinfunction "37_P$37") (pintype "passive"))
      (node (ref "CON2") (pin "P$49") (pinfunction "49_P$49") (pintype "passive"))
      (node (ref "CON2") (pin "P$61") (pinfunction "61_P$61") (pintype "passive"))
    )
    (net (code "6") (name "B1") (class "Default")
      (node (ref "CON1") (pin "P$3") (pinfunction "3_P$3") (pintype "passive"))
      (node (ref "ULN1") (pin "2") (pinfunction "2_2") (pintype "bidirectional"))
    )
    (net (code "7") (name "B2") (class "Default")
      (node (ref "CON1") (pin "P$8") (pinfunction "8_P$8") (pintype "passive"))
      (node (ref "ULN1") (pin "5") (pinfunction "5_5") (pintype "bidirectional"))
    )
    (net (code "8") (name "B3") (class "Default")
      (node (ref "CON1") (pin "P$12") (pinfunction "12_P$12") (pintype "passive"))
      (node (ref "ULN1") (pin "8") (pinfunction "8_8") (pintype "bidirectional"))
    )
    (net (code "9") (name "B4") (class "Default")
      (node (ref "CON1") (pin "P$17") (pinfunction "17_P$17") (pintype "passive"))
      (node (ref "ULN2") (pin "3") (pinfunction "3_3") (pintype "bidirectional"))
    )
    (net (code "10") (name "B5") (class "Default")
      (node (ref "CON1") (pin "P$21") (pinfunction "21_P$21") (pintype "passive"))
      (node (ref "ULN2") (pin "6") (pinfunction "6_6") (pintype "bidirectional"))
    )
    (net (code "11") (name "B6") (class "Default")
      (node (ref "CON1") (pin "P$26") (pinfunction "26_P$26") (pintype "passive"))
      (node (ref "ULN3") (pin "1") (pinfunction "1_1") (pintype "bidirectional"))
    )
    (net (code "12") (name "B7") (class "Default")
      (node (ref "CON1") (pin "P$30") (pinfunction "30_P$30") (pintype "passive"))
      (node (ref "ULN3") (pin "4") (pinfunction "4_4") (pintype "bidirectional"))
    )
    (net (code "13") (name "B8") (class "Default")
      (node (ref "CON1") (pin "P$35") (pinfunction "35_P$35") (pintype "passive"))
      (node (ref "ULN3") (pin "7") (pinfunction "7_7") (pintype "bidirectional"))
    )
    (net (code "14") (name "B9") (class "Default")
      (node (ref "CON1") (pin "P$39") (pinfunction "39_P$39") (pintype "passive"))
      (node (ref "ULN4") (pin "2") (pinfunction "2_2") (pintype "bidirectional"))
    )
    (net (code "15") (name "B10") (class "Default")
      (node (ref "CON1") (pin "P$44") (pinfunction "44_P$44") (pintype "passive"))
      (node (ref "ULN4") (pin "5") (pinfunction "5_5") (pintype "bidirectional"))
    )
    (net (code "16") (name "B11") (class "Default")
      (node (ref "CON1") (pin "P$48") (pinfunction "48_P$48") (pintype "passive"))
      (node (ref "ULN4") (pin "8") (pinfunction "8_8") (pintype "bidirectional"))
    )
    (net (code "17") (name "B12") (class "Default")
      (node (ref "CON1") (pin "P$53") (pinfunction "53_P$53") (pintype "passive"))
      (node (ref "ULN5") (pin "3") (pinfunction "3_3") (pintype "bidirectional"))
    )
    (net (code "18") (name "B13") (class "Default")
      (node (ref "CON1") (pin "P$57") (pinfunction "57_P$57") (pintype "passive"))
      (node (ref "ULN5") (pin "6") (pinfunction "6_6") (pintype "bidirectional"))
    )
    (net (code "19") (name "B14") (class "Default")
      (node (ref "CON1") (pin "P$62") (pinfunction "62_P$62") (pintype "passive"))
      (node (ref "ULN6") (pin "1") (pinfunction "1_1") (pintype "bidirectional"))
    )
    (net (code "20") (name "B15") (class "Default")
      (node (ref "CON1") (pin "P$66") (pinfunction "66_P$66") (pintype "passive"))
      (node (ref "ULN6") (pin "4") (pinfunction "4_4") (pintype "bidirectional"))
    )
    (net (code "21") (name "B16") (class "Default")
      (node (ref "CON1") (pin "P$131") (pinfunction "131_P$131") (pintype "passive"))
      (node (ref "ULN6") (pin "7") (pinfunction "7_7") (pintype "bidirectional"))
    )
    (net (code "22") (name "B17") (class "Default")
      (node (ref "CON1") (pin "P$124") (pinfunction "124_P$124") (pintype "passive"))
      (node (ref "ULN7") (pin "2") (pinfunction "2_2") (pintype "bidirectional"))
    )
    (net (code "23") (name "B18") (class "Default")
      (node (ref "CON1") (pin "P$118") (pinfunction "118_P$118") (pintype "passive"))
      (node (ref "ULN7") (pin "5") (pinfunction "5_5") (pintype "bidirectional"))
    )
    (net (code "24") (name "B19") (class "Default")
      (node (ref "CON1") (pin "P$113") (pinfunction "113_P$113") (pintype "passive"))
      (node (ref "ULN7") (pin "8") (pinfunction "8_8") (pintype "bidirectional"))
    )
    (net (code "25") (name "B20") (class "Default")
      (node (ref "CON2") (pin "P$5") (pinfunction "5_P$5") (pintype "passive"))
      (node (ref "ULN8") (pin "3") (pinfunction "3_3") (pintype "bidirectional"))
    )
    (net (code "26") (name "B21") (class "Default")
      (node (ref "CON2") (pin "P$71") (pinfunction "71_P$71") (pintype "passive"))
      (node (ref "ULN8") (pin "6") (pinfunction "6_6") (pintype "bidirectional"))
    )
    (net (code "27") (name "B22") (class "Default")
      (node (ref "CON2") (pin "P$76") (pinfunction "76_P$76") (pintype "passive"))
      (node (ref "ULN9") (pin "1") (pinfunction "1_1") (pintype "bidirectional"))
    )
    (net (code "28") (name "B23") (class "Default")
      (node (ref "CON2") (pin "P$80") (pinfunction "80_P$80") (pintype "passive"))
      (node (ref "ULN9") (pin "4") (pinfunction "4_4") (pintype "bidirectional"))
    )
    (net (code "29") (name "B24") (class "Default")
      (node (ref "CON2") (pin "P$85") (pinfunction "85_P$85") (pintype "passive"))
      (node (ref "ULN9") (pin "7") (pinfunction "7_7") (pintype "bidirectional"))
    )
    (net (code "30") (name "B25") (class "Default")
      (node (ref "CON2") (pin "P$89") (pinfunction "89_P$89") (pintype "passive"))
      (node (ref "ULN10") (pin "2") (pinfunction "2_2") (pintype "bidirectional"))
    )
    (net (code "31") (name "B26") (class "Default")
      (node (ref "CON2") (pin "P$94") (pinfunction "94_P$94") (pintype "passive"))
      (node (ref "ULN10") (pin "5") (pinfunction "5_5") (pintype "bidirectional"))
    )
    (net (code "32") (name "B27") (class "Default")
      (node (ref "CON2") (pin "P$98") (pinfunction "98_P$98") (pintype "passive"))
      (node (ref "ULN10") (pin "8") (pinfunction "8_8") (pintype "bidirectional"))
    )
    (net (code "33") (name "B28") (class "Default")
      (node (ref "CON2") (pin "P$103") (pinfunction "103_P$103") (pintype "passive"))
      (node (ref "ULN11") (pin "3") (pinfunction "3_3") (pintype "bidirectional"))
    )
    (net (code "34") (name "B29") (class "Default")
      (node (ref "CON2") (pin "P$107") (pinfunction "107_P$107") (pintype "passive"))
      (node (ref "ULN11") (pin "6") (pinfunction "6_6") (pintype "bidirectional"))
    )
    (net (code "35") (name "B30") (class "Default")
      (node (ref "CON2") (pin "P$112") (pinfunction "112_P$112") (pintype "passive"))
      (node (ref "ULN12") (pin "1") (pinfunction "1_1") (pintype "bidirectional"))
    )
    (net (code "36") (name "B31") (class "Default")
      (node (ref "CON2") (pin "P$116") (pinfunction "116_P$116") (pintype "passive"))
      (node (ref "ULN12") (pin "4") (pinfunction "4_4") (pintype "bidirectional"))
    )
    (net (code "37") (name "B32") (class "Default")
      (node (ref "CON2") (pin "P$121") (pinfunction "121_P$121") (pintype "passive"))
      (node (ref "ULN12") (pin "7") (pinfunction "7_7") (pintype "bidirectional"))
    )
    (net (code "38") (name "B33") (class "Default")
      (node (ref "CON2") (pin "P$125") (pinfunction "125_P$125") (pintype "passive"))
      (node (ref "ULN13") (pin "2") (pinfunction "2_2") (pintype "bidirectional"))
    )
    (net (code "39") (name "B34") (class "Default")
      (node (ref "CON2") (pin "P$130") (pinfunction "130_P$130") (pintype "passive"))
      (node (ref "ULN13") (pin "5") (pinfunction "5_5") (pintype "bidirectional"))
    )
    (net (code "40") (name "B35") (class "Default")
      (node (ref "CON2") (pin "P$134") (pinfunction "134_P$134") (pintype "passive"))
      (node (ref "ULN13") (pin "8") (pinfunction "8_8") (pintype "bidirectional"))
    )
    (net (code "41") (name "B36") (class "Default")
      (node (ref "CON2") (pin "P$139") (pinfunction "139_P$139") (pintype "passive"))
      (node (ref "ULN14") (pin "3") (pinfunction "3_3") (pintype "bidirectional"))
    )
    (net (code "42") (name "G1") (class "Default")
      (node (ref "CON1") (pin "P$5") (pinfunction "5_P$5") (pintype "passive"))
      (node (ref "ULN1") (pin "3") (pinfunction "3_3") (pintype "bidirectional"))
    )
    (net (code "43") (name "G2") (class "Default")
      (node (ref "CON1") (pin "P$9") (pinfunction "9_P$9") (pintype "passive"))
      (node (ref "ULN1") (pin "6") (pinfunction "6_6") (pintype "bidirectional"))
    )
    (net (code "44") (name "G3") (class "Default")
      (node (ref "CON1") (pin "P$14") (pinfunction "14_P$14") (pintype "passive"))
      (node (ref "ULN2") (pin "1") (pinfunction "1_1") (pintype "bidirectional"))
    )
    (net (code "45") (name "G4") (class "Default")
      (node (ref "CON1") (pin "P$18") (pinfunction "18_P$18") (pintype "passive"))
      (node (ref "ULN2") (pin "4") (pinfunction "4_4") (pintype "bidirectional"))
    )
    (net (code "46") (name "G5") (class "Default")
      (node (ref "CON1") (pin "P$23") (pinfunction "23_P$23") (pintype "passive"))
      (node (ref "ULN2") (pin "7") (pinfunction "7_7") (pintype "bidirectional"))
    )
    (net (code "47") (name "G6") (class "Default")
      (node (ref "CON1") (pin "P$27") (pinfunction "27_P$27") (pintype "passive"))
      (node (ref "ULN3") (pin "2") (pinfunction "2_2") (pintype "bidirectional"))
    )
    (net (code "48") (name "G7") (class "Default")
      (node (ref "CON1") (pin "P$32") (pinfunction "32_P$32") (pintype "passive"))
      (node (ref "ULN3") (pin "5") (pinfunction "5_5") (pintype "bidirectional"))
    )
    (net (code "49") (name "G8") (class "Default")
      (node (ref "CON1") (pin "P$36") (pinfunction "36_P$36") (pintype "passive"))
      (node (ref "ULN3") (pin "8") (pinfunction "8_8") (pintype "bidirectional"))
    )
    (net (code "50") (name "G9") (class "Default")
      (node (ref "CON1") (pin "P$41") (pinfunction "41_P$41") (pintype "passive"))
      (node (ref "ULN4") (pin "3") (pinfunction "3_3") (pintype "bidirectional"))
    )
    (net (code "51") (name "G10") (class "Default")
      (node (ref "CON1") (pin "P$45") (pinfunction "45_P$45") (pintype "passive"))
      (node (ref "ULN4") (pin "6") (pinfunction "6_6") (pintype "bidirectional"))
    )
    (net (code "52") (name "G11") (class "Default")
      (node (ref "CON1") (pin "P$50") (pinfunction "50_P$50") (pintype "passive"))
      (node (ref "ULN5") (pin "1") (pinfunction "1_1") (pintype "bidirectional"))
    )
    (net (code "53") (name "G12") (class "Default")
      (node (ref "CON1") (pin "P$54") (pinfunction "54_P$54") (pintype "passive"))
      (node (ref "ULN5") (pin "4") (pinfunction "4_4") (pintype "bidirectional"))
    )
    (net (code "54") (name "G13") (class "Default")
      (node (ref "CON1") (pin "P$59") (pinfunction "59_P$59") (pintype "passive"))
      (node (ref "ULN5") (pin "7") (pinfunction "7_7") (pintype "bidirectional"))
    )
    (net (code "55") (name "G14") (class "Default")
      (node (ref "CON1") (pin "P$63") (pinfunction "63_P$63") (pintype "passive"))
      (node (ref "ULN6") (pin "2") (pinfunction "2_2") (pintype "bidirectional"))
    )
    (net (code "56") (name "G15") (class "Default")
      (node (ref "CON1") (pin "P$134") (pinfunction "134_P$134") (pintype "passive"))
      (node (ref "ULN6") (pin "5") (pinfunction "5_5") (pintype "bidirectional"))
    )
    (net (code "57") (name "G16") (class "Default")
      (node (ref "CON1") (pin "P$128") (pinfunction "128_P$128") (pintype "passive"))
      (node (ref "ULN6") (pin "8") (pinfunction "8_8") (pintype "bidirectional"))
    )
    (net (code "58") (name "G17") (class "Default")
      (node (ref "CON1") (pin "P$122") (pinfunction "122_P$122") (pintype "passive"))
      (node (ref "ULN7") (pin "3") (pinfunction "3_3") (pintype "bidirectional"))
    )
    (net (code "59") (name "G18") (class "Default")
      (node (ref "CON1") (pin "P$116") (pinfunction "116_P$116") (pintype "passive"))
      (node (ref "ULN7") (pin "6") (pinfunction "6_6") (pintype "bidirectional"))
    )
    (net (code "60") (name "G19") (class "Default")
      (node (ref "CON2") (pin "P$8") (pinfunction "8_P$8") (pintype "passive"))
      (node (ref "ULN8") (pin "1") (pinfunction "1_1") (pintype "bidirectional"))
    )
    (net (code "61") (name "G20") (class "Default")
      (node (ref "CON2") (pin "P$3") (pinfunction "3_P$3") (pintype "passive"))
      (node (ref "ULN8") (pin "4") (pinfunction "4_4") (pintype "bidirectional"))
    )
    (net (code "62") (name "G21") (class "Default")
      (node (ref "CON2") (pin "P$73") (pinfunction "73_P$73") (pintype "passive"))
      (node (ref "ULN8") (pin "7") (pinfunction "7_7") (pintype "bidirectional"))
    )
    (net (code "63") (name "G22") (class "Default")
      (node (ref "CON2") (pin "P$77") (pinfunction "77_P$77") (pintype "passive"))
      (node (ref "ULN9") (pin "2") (pinfunction "2_2") (pintype "bidirectional"))
    )
    (net (code "64") (name "G23") (class "Default")
      (node (ref "CON2") (pin "P$82") (pinfunction "82_P$82") (pintype "passive"))
      (node (ref "ULN9") (pin "5") (pinfunction "5_5") (pintype "bidirectional"))
    )
    (net (code "65") (name "G24") (class "Default")
      (node (ref "CON2") (pin "P$86") (pinfunction "86_P$86") (pintype "passive"))
      (node (ref "ULN9") (pin "8") (pinfunction "8_8") (pintype "bidirectional"))
    )
    (net (code "66") (name "G25") (class "Default")
      (node (ref "CON2") (pin "P$91") (pinfunction "91_P$91") (pintype "passive"))
      (node (ref "ULN10") (pin "3") (pinfunction "3_3") (pintype "bidirectional"))
    )
    (net (code "67") (name "G26") (class "Default")
      (node (ref "CON2") (pin "P$95") (pinfunction "95_P$95") (pintype "passive"))
      (node (ref "ULN10") (pin "6") (pinfunction "6_6") (pintype "bidirectional"))
    )
    (net (code "68") (name "G27") (class "Default")
      (node (ref "CON2") (pin "P$100") (pinfunction "100_P$100") (pintype "passive"))
      (node (ref "ULN11") (pin "1") (pinfunction "1_1") (pintype "bidirectional"))
    )
    (net (code "69") (name "G28") (class "Default")
      (node (ref "CON2") (pin "P$104") (pinfunction "104_P$104") (pintype "passive"))
      (node (ref "ULN11") (pin "4") (pinfunction "4_4") (pintype "bidirectional"))
    )
    (net (code "70") (name "G29") (class "Default")
      (node (ref "CON2") (pin "P$109") (pinfunction "109_P$109") (pintype "passive"))
      (node (ref "ULN11") (pin "7") (pinfunction "7_7") (pintype "bidirectional"))
    )
    (net (code "71") (name "G30") (class "Default")
      (node (ref "CON2") (pin "P$113") (pinfunction "113_P$113") (pintype "passive"))
      (node (ref "ULN12") (pin "2") (pinfunction "2_2") (pintype "bidirectional"))
    )
    (net (code "72") (name "G31") (class "Default")
      (node (ref "CON2") (pin "P$118") (pinfunction "118_P$118") (pintype "passive"))
      (node (ref "ULN12") (pin "5") (pinfunction "5_5") (pintype "bidirectional"))
    )
    (net (code "73") (name "G32") (class "Default")
      (node (ref "CON2") (pin "P$122") (pinfunction "122_P$122") (pintype "passive"))
      (node (ref "ULN12") (pin "8") (pinfunction "8_8") (pintype "bidirectional"))
    )
    (net (code "74") (name "G33") (class "Default")
      (node (ref "CON2") (pin "P$127") (pinfunction "127_P$127") (pintype "passive"))
      (node (ref "ULN13") (pin "3") (pinfunction "3_3") (pintype "bidirectional"))
    )
    (net (code "75") (name "G34") (class "Default")
      (node (ref "CON2") (pin "P$131") (pinfunction "131_P$131") (pintype "passive"))
      (node (ref "ULN13") (pin "6") (pinfunction "6_6") (pintype "bidirectional"))
    )
    (net (code "76") (name "G35") (class "Default")
      (node (ref "CON2") (pin "P$136") (pinfunction "136_P$136") (pintype "passive"))
      (node (ref "ULN14") (pin "1") (pinfunction "1_1") (pintype "bidirectional"))
    )
    (net (code "77") (name "G36") (class "Default")
      (node (ref "CON2") (pin "P$140") (pinfunction "140_P$140") (pintype "passive"))
      (node (ref "ULN14") (pin "4") (pinfunction "4_4") (pintype "bidirectional"))
    )
    (net (code "78") (name "GND") (class "Default")
      (node (ref "C1") (pin "2") (pinfunction "2_2") (pintype "passive"))
      (node (ref "C10") (pin "2") (pinfunction "2_2") (pintype "passive"))
      (node (ref "C11") (pin "2") (pinfunction "2_2") (pintype "passive"))
      (node (ref "C12") (pin "2") (pinfunction "2_2") (pintype "passive"))
      (node (ref "C13") (pin "2") (pinfunction "2_2") (pintype "passive"))
      (node (ref "C14") (pin "2") (pinfunction "2_2") (pintype "passive"))
      (node (ref "C15") (pin "2") (pinfunction "2_2") (pintype "passive"))
      (node (ref "C16") (pin "2") (pinfunction "2_2") (pintype "passive"))
      (node (ref "C17") (pin "2") (pinfunction "2_2") (pintype "passive"))
      (node (ref "C18") (pin "2") (pinfunction "2_2") (pintype "passive"))
      (node (ref "C19") (pin "2") (pinfunction "2_2") (pintype "passive"))
      (node (ref "C2") (pin "2") (pinfunction "2_2") (pintype "passive"))
      (node (ref "C20") (pin "2") (pinfunction "2_2") (pintype "passive"))
      (node (ref "C21") (pin "2") (pinfunction "2_2") (pintype "passive"))
      (node (ref "C22") (pin "2") (pinfunction "2_2") (pintype "passive"))
      (node (ref "C23") (pin "2") (pinfunction "2_2") (pintype "passive"))
      (node (ref "C24") (pin "2") (pinfunction "2_2") (pintype "passive"))
      (node (ref "C25") (pin "2") (pinfunction "2_2") (pintype "passive"))
      (node (ref "C26") (pin "2") (pinfunction "2_2") (pintype "passive"))
      (node (ref "C27") (pin "-") (pinfunction "-_-") (pintype "passive"))
      (node (ref "C28") (pin "-") (pinfunction "-_-") (pintype "passive"))
      (node (ref "C3") (pin "2") (pinfunction "2_2") (pintype "passive"))
      (node (ref "C4") (pin "2") (pinfunction "2_2") (pintype "passive"))
      (node (ref "C5") (pin "2") (pinfunction "2_2") (pintype "passive"))
      (node (ref "C6") (pin "2") (pinfunction "2_2") (pintype "passive"))
      (node (ref "C7") (pin "2") (pinfunction "2_2") (pintype "passive"))
      (node (ref "C8") (pin "2") (pinfunction "2_2") (pintype "passive"))
      (node (ref "C9") (pin "2") (pinfunction "2_2") (pintype "passive"))
      (node (ref "CON1") (pin "P$10") (pinfunction "10_P$10") (pintype "passive"))
      (node (ref "CON1") (pin "P$105") (pinfunction "105_P$105") (pintype "passive"))
      (node (ref "CON1") (pin "P$108") (pinfunction "108_P$108") (pintype "passive"))
      (node (ref "CON1") (pin "P$111") (pinfunction "111_P$111") (pintype "passive"))
      (node (ref "CON1") (pin "P$117") (pinfunction "117_P$117") (pintype "passive"))
      (node (ref "CON1") (pin "P$120") (pinfunction "120_P$120") (pintype "passive"))
      (node (ref "CON1") (pin "P$123") (pinfunction "123_P$123") (pintype "passive"))
      (node (ref "CON1") (pin "P$129") (pinfunction "129_P$129") (pintype "passive"))
      (node (ref "CON1") (pin "P$132") (pinfunction "132_P$132") (pintype "passive"))
      (node (ref "CON1") (pin "P$135") (pinfunction "135_P$135") (pintype "passive"))
      (node (ref "CON1") (pin "P$16") (pinfunction "16_P$16") (pintype "passive"))
      (node (ref "CON1") (pin "P$19") (pinfunction "19_P$19") (pintype "passive"))
      (node (ref "CON1") (pin "P$22") (pinfunction "22_P$22") (pintype "passive"))
      (node (ref "CON1") (pin "P$28") (pinfunction "28_P$28") (pintype "passive"))
      (node (ref "CON1") (pin "P$31") (pinfunction "31_P$31") (pintype "passive"))
      (node (ref "CON1") (pin "P$34") (pinfunction "34_P$34") (pintype "passive"))
      (node (ref "CON1") (pin "P$4") (pinfunction "4_P$4") (pintype "passive"))
      (node (ref "CON1") (pin "P$40") (pinfunction "40_P$40") (pintype "passive"))
      (node (ref "CON1") (pin "P$43") (pinfunction "43_P$43") (pintype "passive"))
      (node (ref "CON1") (pin "P$46") (pinfunction "46_P$46") (pintype "passive"))
      (node (ref "CON1") (pin "P$52") (pinfunction "52_P$52") (pintype "passive"))
      (node (ref "CON1") (pin "P$55") (pinfunction "55_P$55") (pintype "passive"))
      (node (ref "CON1") (pin "P$58") (pinfunction "58_P$58") (pintype "passive"))
      (node (ref "CON1") (pin "P$64") (pinfunction "64_P$64") (pintype "passive"))
      (node (ref "CON1") (pin "P$67") (pinfunction "67_P$67") (pintype "passive"))
      (node (ref "CON1") (pin "P$7") (pinfunction "7_P$7") (pintype "passive"))
      (node (ref "CON1") (pin "P$70") (pinfunction "70_P$70") (pintype "passive"))
      (node (ref "CON1") (pin "P$72") (pinfunction "72_P$72") (pintype "passive"))
      (node (ref "CON1") (pin "P$75") (pinfunction "75_P$75") (pintype "passive"))
      (node (ref "CON1") (pin "P$81") (pinfunction "81_P$81") (pintype "passive"))
      (node (ref "CON1") (pin "P$84") (pinfunction "84_P$84") (pintype "passive"))
      (node (ref "CON1") (pin "P$87") (pinfunction "87_P$87") (pintype "passive"))
      (node (ref "CON1") (pin "P$93") (pinfunction "93_P$93") (pintype "passive"))
      (node (ref "CON1") (pin "P$96") (pinfunction "96_P$96") (pintype "passive"))
      (node (ref "CON1") (pin "P$99") (pinfunction "99_P$99") (pintype "passive"))
      (node (ref "CON2") (pin "P$10") (pinfunction "10_P$10") (pintype "passive"))
      (node (ref "CON2") (pin "P$105") (pinfunction "105_P$105") (pintype "passive"))
      (node (ref "CON2") (pin "P$108") (pinfunction "108_P$108") (pintype "passive"))
      (node (ref "CON2") (pin "P$111") (pinfunction "111_P$111") (pintype "passive"))
      (node (ref "CON2") (pin "P$117") (pinfunction "117_P$117") (pintype "passive"))
      (node (ref "CON2") (pin "P$120") (pinfunction "120_P$120") (pintype "passive"))
      (node (ref "CON2") (pin "P$123") (pinfunction "123_P$123") (pintype "passive"))
      (node (ref "CON2") (pin "P$129") (pinfunction "129_P$129") (pintype "passive"))
      (node (ref "CON2") (pin "P$132") (pinfunction "132_P$132") (pintype "passive"))
      (node (ref "CON2") (pin "P$135") (pinfunction "135_P$135") (pintype "passive"))
      (node (ref "CON2") (pin "P$16") (pinfunction "16_P$16") (pintype "passive"))
      (node (ref "CON2") (pin "P$19") (pinfunction "19_P$19") (pintype "passive"))
      (node (ref "CON2") (pin "P$22") (pinfunction "22_P$22") (pintype "passive"))
      (node (ref "CON2") (pin "P$28") (pinfunction "28_P$28") (pintype "passive"))
      (node (ref "CON2") (pin "P$31") (pinfunction "31_P$31") (pintype "passive"))
      (node (ref "CON2") (pin "P$34") (pinfunction "34_P$34") (pintype "passive"))
      (node (ref "CON2") (pin "P$4") (pinfunction "4_P$4") (pintype "passive"))
      (node (ref "CON2") (pin "P$40") (pinfunction "40_P$40") (pintype "passive"))
      (node (ref "CON2") (pin "P$43") (pinfunction "43_P$43") (pintype "passive"))
      (node (ref "CON2") (pin "P$46") (pinfunction "46_P$46") (pintype "passive"))
      (node (ref "CON2") (pin "P$52") (pinfunction "52_P$52") (pintype "passive"))
      (node (ref "CON2") (pin "P$55") (pinfunction "55_P$55") (pintype "passive"))
      (node (ref "CON2") (pin "P$58") (pinfunction "58_P$58") (pintype "passive"))
      (node (ref "CON2") (pin "P$64") (pinfunction "64_P$64") (pintype "passive"))
      (node (ref "CON2") (pin "P$67") (pinfunction "67_P$67") (pintype "passive"))
      (node (ref "CON2") (pin "P$7") (pinfunction "7_P$7") (pintype "passive"))
      (node (ref "CON2") (pin "P$70") (pinfunction "70_P$70") (pintype "passive"))
      (node (ref "CON2") (pin "P$72") (pinfunction "72_P$72") (pintype "passive"))
      (node (ref "CON2") (pin "P$75") (pinfunction "75_P$75") (pintype "passive"))
      (node (ref "CON2") (pin "P$81") (pinfunction "81_P$81") (pintype "passive"))
      (node (ref "CON2") (pin "P$84") (pinfunction "84_P$84") (pintype "passive"))
      (node (ref "CON2") (pin "P$87") (pinfunction "87_P$87") (pintype "passive"))
      (node (ref "CON2") (pin "P$93") (pinfunction "93_P$93") (pintype "passive"))
      (node (ref "CON2") (pin "P$96") (pinfunction "96_P$96") (pintype "passive"))
      (node (ref "CON2") (pin "P$99") (pinfunction "99_P$99") (pintype "passive"))
      (node (ref "IC1") (pin "7") (pinfunction "GND_7") (pintype "power_in"))
      (node (ref "PWR") (pin "2") (pinfunction "KL_2") (pintype "passive"))
      (node (ref "ULN1") (pin "9") (pinfunction "9_9") (pintype "bidirectional"))
      (node (ref "ULN10") (pin "9") (pinfunction "9_9") (pintype "bidirectional"))
      (node (ref "ULN11") (pin "9") (pinfunction "9_9") (pintype "bidirectional"))
      (node (ref "ULN12") (pin "9") (pinfunction "9_9") (pintype "bidirectional"))
      (node (ref "ULN13") (pin "9") (pinfunction "9_9") (pintype "bidirectional"))
      (node (ref "ULN14") (pin "5") (pinfunction "5_5") (pintype "bidirectional"))
      (node (ref "ULN14") (pin "6") (pinfunction "6_6") (pintype "bidirectional"))
      (node (ref "ULN14") (pin "7") (pinfunction "7_7") (pintype "bidirectional"))
      (node (ref "ULN14") (pin "8") (pinfunction "8_8") (pintype "bidirectional"))
      (node (ref "ULN14") (pin "9") (pinfunction "9_9") (pintype "bidirectional"))
      (node (ref "ULN2") (pin "9") (pinfunction "9_9") (pintype "bidirectional"))
      (node (ref "ULN3") (pin "9") (pinfunction "9_9") (pintype "bidirectional"))
      (node (ref "ULN4") (pin "9") (pinfunction "9_9") (pintype "bidirectional"))
      (node (ref "ULN5") (pin "9") (pinfunction "9_9") (pintype "bidirectional"))
      (node (ref "ULN6") (pin "9") (pinfunction "9_9") (pintype "bidirectional"))
      (node (ref "ULN7") (pin "9") (pinfunction "9_9") (pintype "bidirectional"))
      (node (ref "ULN8") (pin "9") (pinfunction "9_9") (pintype "bidirectional"))
      (node (ref "ULN9") (pin "9") (pinfunction "9_9") (pintype "bidirectional"))
    )
    (net (code "79") (name "LEVEL_SWITCH_1") (class "Default")
      (node (ref "CON1") (pin "P$71") (pinfunction "71_P$71") (pintype "passive"))
      (node (ref "IC1") (pin "1") (pinfunction "I_1") (pintype "input"))
    )
    (net (code "80") (name "LEVEL_SWITCH_2") (class "Default")
      (node (ref "CON1") (pin "P$73") (pinfunction "73_P$73") (pintype "passive"))
      (node (ref "IC1") (pin "3") (pinfunction "I_3") (pintype "input"))
    )
    (net (code "81") (name "LEVEL_SWITCH_3") (class "Default")
      (node (ref "CON1") (pin "P$74") (pinfunction "74_P$74") (pintype "passive"))
      (node (ref "IC1") (pin "5") (pinfunction "I_5") (pintype "input"))
    )
    (net (code "82") (name "LEVEL_SWITCH_4") (class "Default")
      (node (ref "CON1") (pin "P$76") (pinfunction "76_P$76") (pintype "passive"))
      (node (ref "IC1") (pin "9") (pinfunction "I_9") (pintype "input"))
    )
    (net (code "83") (name "LEVEL_SWITCH_5") (class "Default")
      (node (ref "CON1") (pin "P$77") (pinfunction "77_P$77") (pintype "passive"))
      (node (ref "IC1") (pin "11") (pinfunction "I_11") (pintype "input"))
    )
    (net (code "84") (name "LEVEL_SWITCH_6") (class "Default")
      (node (ref "CON1") (pin "P$79") (pinfunction "79_P$79") (pintype "passive"))
      (node (ref "IC1") (pin "13") (pinfunction "I_13") (pintype "input"))
    )
    (net (code "85") (name "Net-(IC1A-O)") (class "Default")
      (node (ref "IC1") (pin "2") (pinfunction "O_2") (pintype "output"))
      (node (ref "Q1") (pin "1") (pinfunction "G_1") (pintype "passive"))
    )
    (net (code "86") (name "Net-(IC1B-O)") (class "Default")
      (node (ref "IC1") (pin "4") (pinfunction "O_4") (pintype "output"))
      (node (ref "Q2") (pin "1") (pinfunction "G_1") (pintype "passive"))
    )
    (net (code "87") (name "Net-(IC1C-O)") (class "Default")
      (node (ref "IC1") (pin "6") (pinfunction "O_6") (pintype "output"))
      (node (ref "Q3") (pin "1") (pinfunction "G_1") (pintype "passive"))
    )
    (net (code "88") (name "Net-(IC1D-O)") (class "Default")
      (node (ref "IC1") (pin "8") (pinfunction "O_8") (pintype "output"))
      (node (ref "Q4") (pin "1") (pinfunction "G_1") (pintype "passive"))
    )
    (net (code "89") (name "Net-(IC1E-O)") (class "Default")
      (node (ref "IC1") (pin "10") (pinfunction "O_10") (pintype "output"))
      (node (ref "Q5") (pin "1") (pinfunction "G_1") (pintype "passive"))
    )
    (net (code "90") (name "Net-(IC1F-O)") (class "Default")
      (node (ref "IC1") (pin "12") (pinfunction "O_12") (pintype "output"))
      (node (ref "Q6") (pin "1") (pinfunction "G_1") (pintype "passive"))
    )
    (net (code "91") (name "Net-(Q1-D)") (class "Default")
      (node (ref "E1") (pin "1") (pinfunction "1_1") (pintype "passive"))
      (node (ref "EBENE_1") (pin "TP") (pinfunction "TP_TP") (pintype "input"))
      (node (ref "Q1") (pin "3") (pinfunction "D_3") (pintype "passive"))
    )
    (net (code "92") (name "Net-(Q2-D)") (class "Default")
      (node (ref "E2") (pin "1") (pinfunction "1_1") (pintype "passive"))
      (node (ref "EBENE_2") (pin "TP") (pinfunction "TP_TP") (pintype "input"))
      (node (ref "Q2") (pin "3") (pinfunction "D_3") (pintype "passive"))
    )
    (net (code "93") (name "Net-(Q3-D)") (class "Default")
      (node (ref "E3") (pin "1") (pinfunction "1_1") (pintype "passive"))
      (node (ref "EBENE_3") (pin "TP") (pinfunction "TP_TP") (pintype "input"))
      (node (ref "Q3") (pin "3") (pinfunction "D_3") (pintype "passive"))
    )
    (net (code "94") (name "Net-(Q4-D)") (class "Default")
      (node (ref "E4") (pin "1") (pinfunction "1_1") (pintype "passive"))
      (node (ref "EBENE_4") (pin "TP") (pinfunction "TP_TP") (pintype "input"))
      (node (ref "Q4") (pin "3") (pinfunction "D_3") (pintype "passive"))
    )
    (net (code "95") (name "Net-(Q5-D)") (class "Default")
      (node (ref "E5") (pin "1") (pinfunction "1_1") (pintype "passive"))
      (node (ref "EBENE_5") (pin "TP") (pinfunction "TP_TP") (pintype "input"))
      (node (ref "Q5") (pin "3") (pinfunction "D_3") (pintype "passive"))
    )
    (net (code "96") (name "Net-(Q6-D)") (class "Default")
      (node (ref "E6") (pin "1") (pinfunction "1_1") (pintype "passive"))
      (node (ref "EBENE_6") (pin "TP") (pinfunction "TP_TP") (pintype "input"))
      (node (ref "Q6") (pin "3") (pinfunction "D_3") (pintype "passive"))
    )
    (net (code "97") (name "Net-(R1-Pad1)") (class "Default")
      (node (ref "R1") (pin "1") (pinfunction "1_1") (pintype "passive"))
      (node (ref "ULN1") (pin "18") (pinfunction "18_18") (pintype "bidirectional"))
    )
    (net (code "98") (name "Net-(R2-Pad1)") (class "Default")
      (node (ref "R2") (pin "1") (pinfunction "1_1") (pintype "passive"))
      (node (ref "ULN1") (pin "17") (pinfunction "17_17") (pintype "bidirectional"))
    )
    (net (code "99") (name "Net-(R3-Pad1)") (class "Default")
      (node (ref "R3") (pin "1") (pinfunction "1_1") (pintype "passive"))
      (node (ref "ULN1") (pin "16") (pinfunction "16_16") (pintype "bidirectional"))
    )
    (net (code "100") (name "Net-(R4-Pad1)") (class "Default")
      (node (ref "R4") (pin "1") (pinfunction "1_1") (pintype "passive"))
      (node (ref "ULN1") (pin "15") (pinfunction "15_15") (pintype "bidirectional"))
    )
    (net (code "101") (name "Net-(R5-Pad1)") (class "Default")
      (node (ref "R5") (pin "1") (pinfunction "1_1") (pintype "passive"))
      (node (ref "ULN1") (pin "14") (pinfunction "14_14") (pintype "bidirectional"))
    )
    (net (code "102") (name "Net-(R6-Pad1)") (class "Default")
      (node (ref "R6") (pin "1") (pinfunction "1_1") (pintype "passive"))
      (node (ref "ULN1") (pin "13") (pinfunction "13_13") (pintype "bidirectional"))
    )
    (net (code "103") (name "Net-(R7-Pad1)") (class "Default")
      (node (ref "R7") (pin "1") (pinfunction "1_1") (pintype "passive"))
      (node (ref "ULN1") (pin "12") (pinfunction "12_12") (pintype "bidirectional"))
    )
    (net (code "104") (name "Net-(R8-Pad1)") (class "Default")
      (node (ref "R8") (pin "1") (pinfunction "1_1") (pintype "passive"))
      (node (ref "ULN1") (pin "11") (pinfunction "11_11") (pintype "bidirectional"))
    )
    (net (code "105") (name "Net-(R9-Pad1)") (class "Default")
      (node (ref "R9") (pin "1") (pinfunction "1_1") (pintype "passive"))
      (node (ref "ULN2") (pin "18") (pinfunction "18_18") (pintype "bidirectional"))
    )
    (net (code "106") (name "Net-(R10-Pad1)") (class "Default")
      (node (ref "R10") (pin "1") (pinfunction "1_1") (pintype "passive"))
      (node (ref "ULN2") (pin "17") (pinfunction "17_17") (pintype "bidirectional"))
    )
    (net (code "107") (name "Net-(R11-Pad1)") (class "Default")
      (node (ref "R11") (pin "1") (pinfunction "1_1") (pintype "passive"))
      (node (ref "ULN2") (pin "16") (pinfunction "16_16") (pintype "bidirectional"))
    )
    (net (code "108") (name "Net-(R12-Pad1)") (class "Default")
      (node (ref "R12") (pin "1") (pinfunction "1_1") (pintype "passive"))
      (node (ref "ULN2") (pin "15") (pinfunction "15_15") (pintype "bidirectional"))
    )
    (net (code "109") (name "Net-(R13-Pad1)") (class "Default")
      (node (ref "R13") (pin "1") (pinfunction "1_1") (pintype "passive"))
      (node (ref "ULN2") (pin "14") (pinfunction "14_14") (pintype "bidirectional"))
    )
    (net (code "110") (name "Net-(R14-Pad1)") (class "Default")
      (node (ref "R14") (pin "1") (pinfunction "1_1") (pintype "passive"))
      (node (ref "ULN2") (pin "13") (pinfunction "13_13") (pintype "bidirectional"))
    )
    (net (code "111") (name "Net-(R15-Pad1)") (class "Default")
      (node (ref "R15") (pin "1") (pinfunction "1_1") (pintype "passive"))
      (node (ref "ULN2") (pin "12") (pinfunction "12_12") (pintype "bidirectional"))
    )
    (net (code "112") (name "Net-(R16-Pad1)") (class "Default")
      (node (ref "R16") (pin "1") (pinfunction "1_1") (pintype "passive"))
      (node (ref "ULN2") (pin "11") (pinfunction "11_11") (pintype "bidirectional"))
    )
    (net (code "113") (name "Net-(R17-Pad1)") (class "Default")
      (node (ref "R17") (pin "1") (pinfunction "1_1") (pintype "passive"))
      (node (ref "ULN3") (pin "18") (pinfunction "18_18") (pintype "bidirectional"))
    )
    (net (code "114") (name "Net-(R18-Pad1)") (class "Default")
      (node (ref "R18") (pin "1") (pinfunction "1_1") (pintype "passive"))
      (node (ref "ULN3") (pin "17") (pinfunction "17_17") (pintype "bidirectional"))
    )
    (net (code "115") (name "Net-(R19-Pad1)") (class "Default")
      (node (ref "R19") (pin "1") (pinfunction "1_1") (pintype "passive"))
      (node (ref "ULN3") (pin "16") (pinfunction "16_16") (pintype "bidirectional"))
    )
    (net (code "116") (name "Net-(R20-Pad1)") (class "Default")
      (node (ref "R20") (pin "1") (pinfunction "1_1") (pintype "passive"))
      (node (ref "ULN3") (pin "15") (pinfunction "15_15") (pintype "bidirectional"))
    )
    (net (code "117") (name "Net-(R21-Pad1)") (class "Default")
      (node (ref "R21") (pin "1") (pinfunction "1_1") (pintype "passive"))
      (node (ref "ULN3") (pin "14") (pinfunction "14_14") (pintype "bidirectional"))
    )
    (net (code "118") (name "Net-(R22-Pad1)") (class "Default")
      (node (ref "R22") (pin "1") (pinfunction "1_1") (pintype "passive"))
      (node (ref "ULN3") (pin "13") (pinfunction "13_13") (pintype "bidirectional"))
    )
    (net (code "119") (name "Net-(R23-Pad1)") (class "Default")
      (node (ref "R23") (pin "1") (pinfunction "1_1") (pintype "passive"))
      (node (ref "ULN3") (pin "12") (pinfunction "12_12") (pintype "bidirectional"))
    )
    (net (code "120") (name "Net-(R24-Pad1)") (class "Default")
      (node (ref "R24") (pin "1") (pinfunction "1_1") (pintype "passive"))
      (node (ref "ULN3") (pin "11") (pinfunction "11_11") (pintype "bidirectional"))
    )
    (net (code "121") (name "Net-(R25-Pad1)") (class "Default")
      (node (ref "R25") (pin "1") (pinfunction "1_1") (pintype "passive"))
      (node (ref "ULN4") (pin "18") (pinfunction "18_18") (pintype "bidirectional"))
    )
    (net (code "122") (name "Net-(R26-Pad1)") (class "Default")
      (node (ref "R26") (pin "1") (pinfunction "1_1") (pintype "passive"))
      (node (ref "ULN4") (pin "17") (pinfunction "17_17") (pintype "bidirectional"))
    )
    (net (code "123") (name "Net-(R27-Pad1)") (class "Default")
      (node (ref "R27") (pin "1") (pinfunction "1_1") (pintype "passive"))
      (node (ref "ULN4") (pin "16") (pinfunction "16_16") (pintype "bidirectional"))
    )
    (net (code "124") (name "Net-(R28-Pad1)") (class "Default")
      (node (ref "R28") (pin "1") (pinfunction "1_1") (pintype "passive"))
      (node (ref "ULN4") (pin "15") (pinfunction "15_15") (pintype "bidirectional"))
    )
    (net (code "125") (name "Net-(R29-Pad1)") (class "Default")
      (node (ref "R29") (pin "1") (pinfunction "1_1") (pintype "passive"))
      (node (ref "ULN4") (pin "14") (pinfunction "14_14") (pintype "bidirectional"))
    )
    (net (code "126") (name "Net-(R30-Pad1)") (class "Default")
      (node (ref "R30") (pin "1") (pinfunction "1_1") (pintype "passive"))
      (node (ref "ULN4") (pin "13") (pinfunction "13_13") (pintype "bidirectional"))
    )
    (net (code "127") (name "Net-(R31-Pad1)") (class "Default")
      (node (ref "R31") (pin "1") (pinfunction "1_1") (pintype "passive"))
      (node (ref "ULN4") (pin "12") (pinfunction "12_12") (pintype "bidirectional"))
    )
    (net (code "128") (name "Net-(R32-Pad1)") (class "Default")
      (node (ref "R32") (pin "1") (pinfunction "1_1") (pintype "passive"))
      (node (ref "ULN4") (pin "11") (pinfunction "11_11") (pintype "bidirectional"))
    )
    (net (code "129") (name "Net-(R33-Pad1)") (class "Default")
      (node (ref "R33") (pin "1") (pinfunction "1_1") (pintype "passive"))
      (node (ref "ULN5") (pin "18") (pinfunction "18_18") (pintype "bidirectional"))
    )
    (net (code "130") (name "Net-(R34-Pad1)") (class "Default")
      (node (ref "R34") (pin "1") (pinfunction "1_1") (pintype "passive"))
      (node (ref "ULN5") (pin "17") (pinfunction "17_17") (pintype "bidirectional"))
    )
    (net (code "131") (name "Net-(R35-Pad1)") (class "Default")
      (node (ref "R35") (pin "1") (pinfunction "1_1") (pintype "passive"))
      (node (ref "ULN5") (pin "16") (pinfunction "16_16") (pintype "bidirectional"))
    )
    (net (code "132") (name "Net-(R36-Pad1)") (class "Default")
      (node (ref "R36") (pin "1") (pinfunction "1_1") (pintype "passive"))
      (node (ref "ULN5") (pin "15") (pinfunction "15_15") (pintype "bidirectional"))
    )
    (net (code "133") (name "Net-(R37-Pad1)") (class "Default")
      (node (ref "R37") (pin "1") (pinfunction "1_1") (pintype "passive"))
      (node (ref "ULN5") (pin "14") (pinfunction "14_14") (pintype "bidirectional"))
    )
    (net (code "134") (name "Net-(R38-Pad1)") (class "Default")
      (node (ref "R38") (pin "1") (pinfunction "1_1") (pintype "passive"))
      (node (ref "ULN5") (pin "13") (pinfunction "13_13") (pintype "bidirectional"))
    )
    (net (code "135") (name "Net-(R39-Pad1)") (class "Default")
      (node (ref "R39") (pin "1") (pinfunction "1_1") (pintype "passive"))
      (node (ref "ULN5") (pin "12") (pinfunction "12_12") (pintype "bidirectional"))
    )
    (net (code "136") (name "Net-(R40-Pad1)") (class "Default")
      (node (ref "R40") (pin "1") (pinfunction "1_1") (pintype "passive"))
      (node (ref "ULN5") (pin "11") (pinfunction "11_11") (pintype "bidirectional"))
    )
    (net (code "137") (name "Net-(R41-Pad1)") (class "Default")
      (node (ref "R41") (pin "1") (pinfunction "1_1") (pintype "passive"))
      (node (ref "ULN6") (pin "18") (pinfunction "18_18") (pintype "bidirectional"))
    )
    (net (code "138") (name "Net-(R42-Pad1)") (class "Default")
      (node (ref "R42") (pin "1") (pinfunction "1_1") (pintype "passive"))
      (node (ref "ULN6") (pin "17") (pinfunction "17_17") (pintype "bidirectional"))
    )
    (net (code "139") (name "Net-(R43-Pad1)") (class "Default")
      (node (ref "R43") (pin "1") (pinfunction "1_1") (pintype "passive"))
      (node (ref "ULN6") (pin "16") (pinfunction "16_16") (pintype "bidirectional"))
    )
    (net (code "140") (name "Net-(R44-Pad1)") (class "Default")
      (node (ref "R44") (pin "1") (pinfunction "1_1") (pintype "passive"))
      (node (ref "ULN6") (pin "15") (pinfunction "15_15") (pintype "bidirectional"))
    )
    (net (code "141") (name "Net-(R45-Pad1)") (class "Default")
      (node (ref "R45") (pin "1") (pinfunction "1_1") (pintype "passive"))
      (node (ref "ULN6") (pin "14") (pinfunction "14_14") (pintype "bidirectional"))
    )
    (net (code "142") (name "Net-(R46-Pad1)") (class "Default")
      (node (ref "R46") (pin "1") (pinfunction "1_1") (pintype "passive"))
      (node (ref "ULN6") (pin "13") (pinfunction "13_13") (pintype "bidirectional"))
    )
    (net (code "143") (name "Net-(R47-Pad1)") (class "Default")
      (node (ref "R47") (pin "1") (pinfunction "1_1") (pintype "passive"))
      (node (ref "ULN6") (pin "12") (pinfunction "12_12") (pintype "bidirectional"))
    )
    (net (code "144") (name "Net-(R48-Pad1)") (class "Default")
      (node (ref "R48") (pin "1") (pinfunction "1_1") (pintype "passive"))
      (node (ref "ULN6") (pin "11") (pinfunction "11_11") (pintype "bidirectional"))
    )
    (net (code "145") (name "Net-(R49-Pad1)") (class "Default")
      (node (ref "R49") (pin "1") (pinfunction "1_1") (pintype "passive"))
      (node (ref "ULN7") (pin "18") (pinfunction "18_18") (pintype "bidirectional"))
    )
    (net (code "146") (name "Net-(R50-Pad1)") (class "Default")
      (node (ref "R50") (pin "1") (pinfunction "1_1") (pintype "passive"))
      (node (ref "ULN7") (pin "17") (pinfunction "17_17") (pintype "bidirectional"))
    )
    (net (code "147") (name "Net-(R51-Pad1)") (class "Default")
      (node (ref "R51") (pin "1") (pinfunction "1_1") (pintype "passive"))
      (node (ref "ULN7") (pin "16") (pinfunction "16_16") (pintype "bidirectional"))
    )
    (net (code "148") (name "Net-(R52-Pad1)") (class "Default")
      (node (ref "R52") (pin "1") (pinfunction "1_1") (pintype "passive"))
      (node (ref "ULN7") (pin "15") (pinfunction "15_15") (pintype "bidirectional"))
    )
    (net (code "149") (name "Net-(R53-Pad1)") (class "Default")
      (node (ref "R53") (pin "1") (pinfunction "1_1") (pintype "passive"))
      (node (ref "ULN7") (pin "14") (pinfunction "14_14") (pintype "bidirectional"))
    )
    (net (code "150") (name "Net-(R54-Pad1)") (class "Default")
      (node (ref "R54") (pin "1") (pinfunction "1_1") (pintype "passive"))
      (node (ref "ULN7") (pin "13") (pinfunction "13_13") (pintype "bidirectional"))
    )
    (net (code "151") (name "Net-(R55-Pad1)") (class "Default")
      (node (ref "R55") (pin "1") (pinfunction "1_1") (pintype "passive"))
      (node (ref "ULN7") (pin "12") (pinfunction "12_12") (pintype "bidirectional"))
    )
    (net (code "152") (name "Net-(R56-Pad1)") (class "Default")
      (node (ref "R56") (pin "1") (pinfunction "1_1") (pintype "passive"))
      (node (ref "ULN7") (pin "11") (pinfunction "11_11") (pintype "bidirectional"))
    )
    (net (code "153") (name "Net-(R57-Pad1)") (class "Default")
      (node (ref "R57") (pin "1") (pinfunction "1_1") (pintype "passive"))
      (node (ref "ULN8") (pin "18") (pinfunction "18_18") (pintype "bidirectional"))
    )
    (net (code "154") (name "Net-(R58-Pad1)") (class "Default")
      (node (ref "R58") (pin "1") (pinfunction "1_1") (pintype "passive"))
      (node (ref "ULN8") (pin "17") (pinfunction "17_17") (pintype "bidirectional"))
    )
    (net (code "155") (name "Net-(R59-Pad1)") (class "Default")
      (node (ref "R59") (pin "1") (pinfunction "1_1") (pintype "passive"))
      (node (ref "ULN8") (pin "16") (pinfunction "16_16") (pintype "bidirectional"))
    )
    (net (code "156") (name "Net-(R60-Pad1)") (class "Default")
      (node (ref "R60") (pin "1") (pinfunction "1_1") (pintype "passive"))
      (node (ref "ULN8") (pin "15") (pinfunction "15_15") (pintype "bidirectional"))
    )
    (net (code "157") (name "Net-(R61-Pad1)") (class "Default")
      (node (ref "R61") (pin "1") (pinfunction "1_1") (pintype "passive"))
      (node (ref "ULN8") (pin "14") (pinfunction "14_14") (pintype "bidirectional"))
    )
    (net (code "158") (name "Net-(R62-Pad1)") (class "Default")
      (node (ref "R62") (pin "1") (pinfunction "1_1") (pintype "passive"))
      (node (ref "ULN8") (pin "13") (pinfunction "13_13") (pintype "bidirectional"))
    )
    (net (code "159") (name "Net-(R63-Pad1)") (class "Default")
      (node (ref "R63") (pin "1") (pinfunction "1_1") (pintype "passive"))
      (node (ref "ULN8") (pin "12") (pinfunction "12_12") (pintype "bidirectional"))
    )
    (net (code "160") (name "Net-(R64-Pad1)") (class "Default")
      (node (ref "R64") (pin "1") (pinfunction "1_1") (pintype "passive"))
      (node (ref "ULN8") (pin "11") (pinfunction "11_11") (pintype "bidirectional"))
    )
    (net (code "161") (name "Net-(R65-Pad1)") (class "Default")
      (node (ref "R65") (pin "1") (pinfunction "1_1") (pintype "passive"))
      (node (ref "ULN9") (pin "18") (pinfunction "18_18") (pintype "bidirectional"))
    )
    (net (code "162") (name "Net-(R66-Pad1)") (class "Default")
      (node (ref "R66") (pin "1") (pinfunction "1_1") (pintype "passive"))
      (node (ref "ULN9") (pin "17") (pinfunction "17_17") (pintype "bidirectional"))
    )
    (net (code "163") (name "Net-(R67-Pad1)") (class "Default")
      (node (ref "R67") (pin "1") (pinfunction "1_1") (pintype "passive"))
      (node (ref "ULN9") (pin "16") (pinfunction "16_16") (pintype "bidirectional"))
    )
    (net (code "164") (name "Net-(R68-Pad1)") (class "Default")
      (node (ref "R68") (pin "1") (pinfunction "1_1") (pintype "passive"))
      (node (ref "ULN9") (pin "15") (pinfunction "15_15") (pintype "bidirectional"))
    )
    (net (code "165") (name "Net-(R69-Pad1)") (class "Default")
      (node (ref "R69") (pin "1") (pinfunction "1_1") (pintype "passive"))
      (node (ref "ULN9") (pin "14") (pinfunction "14_14") (pintype "bidirectional"))
    )
    (net (code "166") (name "Net-(R70-Pad1)") (class "Default")
      (node (ref "R70") (pin "1") (pinfunction "1_1") (pintype "passive"))
      (node (ref "ULN9") (pin "13") (pinfunction "13_13") (pintype "bidirectional"))
    )
    (net (code "167") (name "Net-(R71-Pad1)") (class "Default")
      (node (ref "R71") (pin "1") (pinfunction "1_1") (pintype "passive"))
      (node (ref "ULN9") (pin "12") (pinfunction "12_12") (pintype "bidirectional"))
    )
    (net (code "168") (name "Net-(R72-Pad1)") (class "Default")
      (node (ref "R72") (pin "1") (pinfunction "1_1") (pintype "passive"))
      (node (ref "ULN9") (pin "11") (pinfunction "11_11") (pintype "bidirectional"))
    )
    (net (code "169") (name "Net-(R73-Pad1)") (class "Default")
      (node (ref "R73") (pin "1") (pinfunction "1_1") (pintype "passive"))
      (node (ref "ULN10") (pin "18") (pinfunction "18_18") (pintype "bidirectional"))
    )
    (net (code "170") (name "Net-(R74-Pad1)") (class "Default")
      (node (ref "R74") (pin "1") (pinfunction "1_1") (pintype "passive"))
      (node (ref "ULN10") (pin "17") (pinfunction "17_17") (pintype "bidirectional"))
    )
    (net (code "171") (name "Net-(R75-Pad1)") (class "Default")
      (node (ref "R75") (pin "1") (pinfunction "1_1") (pintype "passive"))
      (node (ref "ULN10") (pin "16") (pinfunction "16_16") (pintype "bidirectional"))
    )
    (net (code "172") (name "Net-(R76-Pad1)") (class "Default")
      (node (ref "R76") (pin "1") (pinfunction "1_1") (pintype "passive"))
      (node (ref "ULN10") (pin "15") (pinfunction "15_15") (pintype "bidirectional"))
    )
    (net (code "173") (name "Net-(R77-Pad1)") (class "Default")
      (node (ref "R77") (pin "1") (pinfunction "1_1") (pintype "passive"))
      (node (ref "ULN10") (pin "14") (pinfunction "14_14") (pintype "bidirectional"))
    )
    (net (code "174") (name "Net-(R78-Pad1)") (class "Default")
      (node (ref "R78") (pin "1") (pinfunction "1_1") (pintype "passive"))
      (node (ref "ULN10") (pin "13") (pinfunction "13_13") (pintype "bidirectional"))
    )
    (net (code "175") (name "Net-(R79-Pad1)") (class "Default")
      (node (ref "R79") (pin "1") (pinfunction "1_1") (pintype "passive"))
      (node (ref "ULN10") (pin "12") (pinfunction "12_12") (pintype "bidirectional"))
    )
    (net (code "176") (name "Net-(R80-Pad1)") (class "Default")
      (node (ref "R80") (pin "1") (pinfunction "1_1") (pintype "passive"))
      (node (ref "ULN10") (pin "11") (pinfunction "11_11") (pintype "bidirectional"))
    )
    (net (code "177") (name "Net-(R81-Pad1)") (class "Default")
      (node (ref "R81") (pin "1") (pinfunction "1_1") (pintype "passive"))
      (node (ref "ULN11") (pin "18") (pinfunction "18_18") (pintype "bidirectional"))
    )
    (net (code "178") (name "Net-(R82-Pad1)") (class "Default")
      (node (ref "R82") (pin "1") (pinfunction "1_1") (pintype "passive"))
      (node (ref "ULN11") (pin "17") (pinfunction "17_17") (pintype "bidirectional"))
    )
    (net (code "179") (name "Net-(R83-Pad1)") (class "Default")
      (node (ref "R83") (pin "1") (pinfunction "1_1") (pintype "passive"))
      (node (ref "ULN11") (pin "16") (pinfunction "16_16") (pintype "bidirectional"))
    )
    (net (code "180") (name "Net-(R84-Pad1)") (class "Default")
      (node (ref "R84") (pin "1") (pinfunction "1_1") (pintype "passive"))
      (node (ref "ULN11") (pin "15") (pinfunction "15_15") (pintype "bidirectional"))
    )
    (net (code "181") (name "Net-(R85-Pad1)") (class "Default")
      (node (ref "R85") (pin "1") (pinfunction "1_1") (pintype "passive"))
      (node (ref "ULN11") (pin "14") (pinfunction "14_14") (pintype "bidirectional"))
    )
    (net (code "182") (name "Net-(R86-Pad1)") (class "Default")
      (node (ref "R86") (pin "1") (pinfunction "1_1") (pintype "passive"))
      (node (ref "ULN11") (pin "13") (pinfunction "13_13") (pintype "bidirectional"))
    )
    (net (code "183") (name "Net-(R87-Pad1)") (class "Default")
      (node (ref "R87") (pin "1") (pinfunction "1_1") (pintype "passive"))
      (node (ref "ULN11") (pin "12") (pinfunction "12_12") (pintype "bidirectional"))
    )
    (net (code "184") (name "Net-(R88-Pad1)") (class "Default")
      (node (ref "R88") (pin "1") (pinfunction "1_1") (pintype "passive"))
      (node (ref "ULN11") (pin "11") (pinfunction "11_11") (pintype "bidirectional"))
    )
    (net (code "185") (name "Net-(R89-Pad1)") (class "Default")
      (node (ref "R89") (pin "1") (pinfunction "1_1") (pintype "passive"))
      (node (ref "ULN12") (pin "18") (pinfunction "18_18") (pintype "bidirectional"))
    )
    (net (code "186") (name "Net-(R90-Pad1)") (class "Default")
      (node (ref "R90") (pin "1") (pinfunction "1_1") (pintype "passive"))
      (node (ref "ULN12") (pin "17") (pinfunction "17_17") (pintype "bidirectional"))
    )
    (net (code "187") (name "Net-(R91-Pad1)") (class "Default")
      (node (ref "R91") (pin "1") (pinfunction "1_1") (pintype "passive"))
      (node (ref "ULN12") (pin "16") (pinfunction "16_16") (pintype "bidirectional"))
    )
    (net (code "188") (name "Net-(R92-Pad1)") (class "Default")
      (node (ref "R92") (pin "1") (pinfunction "1_1") (pintype "passive"))
      (node (ref "ULN12") (pin "15") (pinfunction "15_15") (pintype "bidirectional"))
    )
    (net (code "189") (name "Net-(R93-Pad1)") (class "Default")
      (node (ref "R93") (pin "1") (pinfunction "1_1") (pintype "passive"))
      (node (ref "ULN12") (pin "14") (pinfunction "14_14") (pintype "bidirectional"))
    )
    (net (code "190") (name "Net-(R94-Pad1)") (class "Default")
      (node (ref "R94") (pin "1") (pinfunction "1_1") (pintype "passive"))
      (node (ref "ULN12") (pin "13") (pinfunction "13_13") (pintype "bidirectional"))
    )
    (net (code "191") (name "Net-(R95-Pad1)") (class "Default")
      (node (ref "R95") (pin "1") (pinfunction "1_1") (pintype "passive"))
      (node (ref "ULN12") (pin "12") (pinfunction "12_12") (pintype "bidirectional"))
    )
    (net (code "192") (name "Net-(R96-Pad1)") (class "Default")
      (node (ref "R96") (pin "1") (pinfunction "1_1") (pintype "passive"))
      (node (ref "ULN12") (pin "11") (pinfunction "11_11") (pintype "bidirectional"))
    )
    (net (code "193") (name "Net-(R97-Pad1)") (class "Default")
      (node (ref "R97") (pin "1") (pinfunction "1_1") (pintype "passive"))
      (node (ref "ULN13") (pin "18") (pinfunction "18_18") (pintype "bidirectional"))
    )
    (net (code "194") (name "Net-(R98-Pad1)") (class "Default")
      (node (ref "R98") (pin "1") (pinfunction "1_1") (pintype "passive"))
      (node (ref "ULN13") (pin "17") (pinfunction "17_17") (pintype "bidirectional"))
    )
    (net (code "195") (name "Net-(R99-Pad1)") (class "Default")
      (node (ref "R99") (pin "1") (pinfunction "1_1") (pintype "passive"))
      (node (ref "ULN13") (pin "16") (pinfunction "16_16") (pintype "bidirectional"))
    )
    (net (code "196") (name "Net-(R100-Pad1)") (class "Default")
      (node (ref "R100") (pin "1") (pinfunction "1_1") (pintype "passive"))
      (node (ref "ULN13") (pin "15") (pinfunction "15_15") (pintype "bidirectional"))
    )
    (net (code "197") (name "Net-(R101-Pad1)") (class "Default")
      (node (ref "R101") (pin "1") (pinfunction "1_1") (pintype "passive"))
      (node (ref "ULN13") (pin "14") (pinfunction "14_14") (pintype "bidirectional"))
    )
    (net (code "198") (name "Net-(R102-Pad1)") (class "Default")
      (node (ref "R102") (pin "1") (pinfunction "1_1") (pintype "passive"))
      (node (ref "ULN13") (pin "13") (pinfunction "13_13") (pintype "bidirectional"))
    )
    (net (code "199") (name "Net-(R103-Pad1)") (class "Default")
      (node (ref "R103") (pin "1") (pinfunction "1_1") (pintype "passive"))
      (node (ref "ULN13") (pin "12") (pinfunction "12_12") (pintype "bidirectional"))
    )
    (net (code "200") (name "Net-(R104-Pad1)") (class "Default")
      (node (ref "R104") (pin "1") (pinfunction "1_1") (pintype "passive"))
      (node (ref "ULN13") (pin "11") (pinfunction "11_11") (pintype "bidirectional"))
    )
    (net (code "201") (name "Net-(R105-Pad1)") (class "Default")
      (node (ref "R105") (pin "1") (pinfunction "1_1") (pintype "passive"))
      (node (ref "ULN14") (pin "18") (pinfunction "18_18") (pintype "bidirectional"))
    )
    (net (code "202") (name "Net-(R106-Pad1)") (class "Default")
      (node (ref "R106") (pin "1") (pinfunction "1_1") (pintype "passive"))
      (node (ref "ULN14") (pin "17") (pinfunction "17_17") (pintype "bidirectional"))
    )
    (net (code "203") (name "Net-(R107-Pad1)") (class "Default")
      (node (ref "R107") (pin "1") (pinfunction "1_1") (pintype "passive"))
      (node (ref "ULN14") (pin "16") (pinfunction "16_16") (pintype "bidirectional"))
    )
    (net (code "204") (name "Net-(R108-Pad1)") (class "Default")
      (node (ref "R108") (pin "1") (pinfunction "1_1") (pintype "passive"))
      (node (ref "ULN14") (pin "15") (pinfunction "15_15") (pintype "bidirectional"))
    )
    (net (code "205") (name "Net-(RGB1-BLUE_CATHODE)") (class "Default")
      (node (ref "R2") (pin "2") (pinfunction "2_2") (pintype "passive"))
      (node (ref "RGB1") (pin "B") (pinfunction "BLUE_CATHODE_B") (pintype "bidirectional"))
    )
    (net (code "206") (name "Net-(RGB1-GREEN_CATHODE)") (class "Default")
      (node (ref "R3") (pin "2") (pinfunction "2_2") (pintype "passive"))
      (node (ref "RGB1") (pin "G") (pinfunction "GREEN_CATHODE_G") (pintype "bidirectional"))
    )
    (net (code "207") (name "Net-(RGB1-RED_CATHODE)") (class "Default")
      (node (ref "R1") (pin "2") (pinfunction "2_2") (pintype "passive"))
      (node (ref "RGB1") (pin "R") (pinfunction "RED_CATHODE_R") (pintype "bidirectional"))
    )
    (net (code "208") (name "Net-(RGB2-BLUE_CATHODE)") (class "Default")
      (node (ref "R5") (pin "2") (pinfunction "2_2") (pintype "passive"))
      (node (ref "RGB2") (pin "B") (pinfunction "BLUE_CATHODE_B") (pintype "bidirectional"))
    )
    (net (code "209") (name "Net-(RGB2-GREEN_CATHODE)") (class "Default")
      (node (ref "R6") (pin "2") (pinfunction "2_2") (pintype "passive"))
      (node (ref "RGB2") (pin "G") (pinfunction "GREEN_CATHODE_G") (pintype "bidirectional"))
    )
    (net (code "210") (name "Net-(RGB2-RED_CATHODE)") (class "Default")
      (node (ref "R4") (pin "2") (pinfunction "2_2") (pintype "passive"))
      (node (ref "RGB2") (pin "R") (pinfunction "RED_CATHODE_R") (pintype "bidirectional"))
    )
    (net (code "211") (name "Net-(RGB3-BLUE_CATHODE)") (class "Default")
      (node (ref "R8") (pin "2") (pinfunction "2_2") (pintype "passive"))
      (node (ref "RGB3") (pin "B") (pinfunction "BLUE_CATHODE_B") (pintype "bidirectional"))
    )
    (net (code "212") (name "Net-(RGB3-GREEN_CATHODE)") (class "Default")
      (node (ref "R9") (pin "2") (pinfunction "2_2") (pintype "passive"))
      (node (ref "RGB3") (pin "G") (pinfunction "GREEN_CATHODE_G") (pintype "bidirectional"))
    )
    (net (code "213") (name "Net-(RGB3-RED_CATHODE)") (class "Default")
      (node (ref "R7") (pin "2") (pinfunction "2_2") (pintype "passive"))
      (node (ref "RGB3") (pin "R") (pinfunction "RED_CATHODE_R") (pintype "bidirectional"))
    )
    (net (code "214") (name "Net-(RGB4-BLUE_CATHODE)") (class "Default")
      (node (ref "R11") (pin "2") (pinfunction "2_2") (pintype "passive"))
      (node (ref "RGB4") (pin "B") (pinfunction "BLUE_CATHODE_B") (pintype "bidirectional"))
    )
    (net (code "215") (name "Net-(RGB4-GREEN_CATHODE)") (class "Default")
      (node (ref "R12") (pin "2") (pinfunction "2_2") (pintype "passive"))
      (node (ref "RGB4") (pin "G") (pinfunction "GREEN_CATHODE_G") (pintype "bidirectional"))
    )
    (net (code "216") (name "Net-(RGB4-RED_CATHODE)") (class "Default")
      (node (ref "R10") (pin "2") (pinfunction "2_2") (pintype "passive"))
      (node (ref "RGB4") (pin "R") (pinfunction "RED_CATHODE_R") (pintype "bidirectional"))
    )
    (net (code "217") (name "Net-(RGB5-BLUE_CATHODE)") (class "Default")
      (node (ref "R14") (pin "2") (pinfunction "2_2") (pintype "passive"))
      (node (ref "RGB5") (pin "B") (pinfunction "BLUE_CATHODE_B") (pintype "bidirectional"))
    )
    (net (code "218") (name "Net-(RGB5-GREEN_CATHODE)") (class "Default")
      (node (ref "R15") (pin "2") (pinfunction "2_2") (pintype "passive"))
      (node (ref "RGB5") (pin "G") (pinfunction "GREEN_CATHODE_G") (pintype "bidirectional"))
    )
    (net (code "219") (name "Net-(RGB5-RED_CATHODE)") (class "Default")
      (node (ref "R13") (pin "2") (pinfunction "2_2") (pintype "passive"))
      (node (ref "RGB5") (pin "R") (pinfunction "RED_CATHODE_R") (pintype "bidirectional"))
    )
    (net (code "220") (name "Net-(RGB6-BLUE_CATHODE)") (class "Default")
      (node (ref "R17") (pin "2") (pinfunction "2_2") (pintype "passive"))
      (node (ref "RGB6") (pin "B") (pinfunction "BLUE_CATHODE_B") (pintype "bidirectional"))
    )
    (net (code "221") (name "Net-(RGB6-GREEN_CATHODE)") (class "Default")
      (node (ref "R18") (pin "2") (pinfunction "2_2") (pintype "passive"))
      (node (ref "RGB6") (pin "G") (pinfunction "GREEN_CATHODE_G") (pintype "bidirectional"))
    )
    (net (code "222") (name "Net-(RGB6-RED_CATHODE)") (class "Default")
      (node (ref "R16") (pin "2") (pinfunction "2_2") (pintype "passive"))
      (node (ref "RGB6") (pin "R") (pinfunction "RED_CATHODE_R") (pintype "bidirectional"))
    )
    (net (code "223") (name "Net-(RGB7-BLUE_CATHODE)") (class "Default")
      (node (ref "R20") (pin "2") (pinfunction "2_2") (pintype "passive"))
      (node (ref "RGB7") (pin "B") (pinfunction "BLUE_CATHODE_B") (pintype "bidirectional"))
    )
    (net (code "224") (name "Net-(RGB7-GREEN_CATHODE)") (class "Default")
      (node (ref "R21") (pin "2") (pinfunction "2_2") (pintype "passive"))
      (node (ref "RGB7") (pin "G") (pinfunction "GREEN_CATHODE_G") (pintype "bidirectional"))
    )
    (net (code "225") (name "Net-(RGB7-RED_CATHODE)") (class "Default")
      (node (ref "R19") (pin "2") (pinfunction "2_2") (pintype "passive"))
      (node (ref "RGB7") (pin "R") (pinfunction "RED_CATHODE_R") (pintype "bidirectional"))
    )
    (net (code "226") (name "Net-(RGB8-BLUE_CATHODE)") (class "Default")
      (node (ref "R23") (pin "2") (pinfunction "2_2") (pintype "passive"))
      (node (ref "RGB8") (pin "B") (pinfunction "BLUE_CATHODE_B") (pintype "bidirectional"))
    )
    (net (code "227") (name "Net-(RGB8-GREEN_CATHODE)") (class "Default")
      (node (ref "R24") (pin "2") (pinfunction "2_2") (pintype "passive"))
      (node (ref "RGB8") (pin "G") (pinfunction "GREEN_CATHODE_G") (pintype "bidirectional"))
    )
    (net (code "228") (name "Net-(RGB8-RED_CATHODE)") (class "Default")
      (node (ref "R22") (pin "2") (pinfunction "2_2") (pintype "passive"))
      (node (ref "RGB8") (pin "R") (pinfunction "RED_CATHODE_R") (pintype "bidirectional"))
    )
    (net (code "229") (name "Net-(RGB9-BLUE_CATHODE)") (class "Default")
      (node (ref "R26") (pin "2") (pinfunction "2_2") (pintype "passive"))
      (node (ref "RGB9") (pin "B") (pinfunction "BLUE_CATHODE_B") (pintype "bidirectional"))
    )
    (net (code "230") (name "Net-(RGB9-GREEN_CATHODE)") (class "Default")
      (node (ref "R27") (pin "2") (pinfunction "2_2") (pintype "passive"))
      (node (ref "RGB9") (pin "G") (pinfunction "GREEN_CATHODE_G") (pintype "bidirectional"))
    )
    (net (code "231") (name "Net-(RGB9-RED_CATHODE)") (class "Default")
      (node (ref "R25") (pin "2") (pinfunction "2_2") (pintype "passive"))
      (node (ref "RGB9") (pin "R") (pinfunction "RED_CATHODE_R") (pintype "bidirectional"))
    )
    (net (code "232") (name "Net-(RGB10-BLUE_CATHODE)") (class "Default")
      (node (ref "R29") (pin "2") (pinfunction "2_2") (pintype "passive"))
      (node (ref "RGB10") (pin "B") (pinfunction "BLUE_CATHODE_B") (pintype "bidirectional"))
    )
    (net (code "233") (name "Net-(RGB10-GREEN_CATHODE)") (class "Default")
      (node (ref "R30") (pin "2") (pinfunction "2_2") (pintype "passive"))
      (node (ref "RGB10") (pin "G") (pinfunction "GREEN_CATHODE_G") (pintype "bidirectional"))
    )
    (net (code "234") (name "Net-(RGB10-RED_CATHODE)") (class "Default")
      (node (ref "R28") (pin "2") (pinfunction "2_2") (pintype "passive"))
      (node (ref "RGB10") (pin "R") (pinfunction "RED_CATHODE_R") (pintype "bidirectional"))
    )
    (net (code "235") (name "Net-(RGB11-BLUE_CATHODE)") (class "Default")
      (node (ref "R32") (pin "2") (pinfunction "2_2") (pintype "passive"))
      (node (ref "RGB11") (pin "B") (pinfunction "BLUE_CATHODE_B") (pintype "bidirectional"))
    )
    (net (code "236") (name "Net-(RGB11-GREEN_CATHODE)") (class "Default")
      (node (ref "R33") (pin "2") (pinfunction "2_2") (pintype "passive"))
      (node (ref "RGB11") (pin "G") (pinfunction "GREEN_CATHODE_G") (pintype "bidirectional"))
    )
    (net (code "237") (name "Net-(RGB11-RED_CATHODE)") (class "Default")
      (node (ref "R31") (pin "2") (pinfunction "2_2") (pintype "passive"))
      (node (ref "RGB11") (pin "R") (pinfunction "RED_CATHODE_R") (pintype "bidirectional"))
    )
    (net (code "238") (name "Net-(RGB12-BLUE_CATHODE)") (class "Default")
      (node (ref "R35") (pin "2") (pinfunction "2_2") (pintype "passive"))
      (node (ref "RGB12") (pin "B") (pinfunction "BLUE_CATHODE_B") (pintype "bidirectional"))
    )
    (net (code "239") (name "Net-(RGB12-GREEN_CATHODE)") (class "Default")
      (node (ref "R36") (pin "2") (pinfunction "2_2") (pintype "passive"))
      (node (ref "RGB12") (pin "G") (pinfunction "GREEN_CATHODE_G") (pintype "bidirectional"))
    )
    (net (code "240") (name "Net-(RGB12-RED_CATHODE)") (class "Default")
      (node (ref "R34") (pin "2") (pinfunction "2_2") (pintype "passive"))
      (node (ref "RGB12") (pin "R") (pinfunction "RED_CATHODE_R") (pintype "bidirectional"))
    )
    (net (code "241") (name "Net-(RGB13-BLUE_CATHODE)") (class "Default")
      (node (ref "R38") (pin "2") (pinfunction "2_2") (pintype "passive"))
      (node (ref "RGB13") (pin "B") (pinfunction "BLUE_CATHODE_B") (pintype "bidirectional"))
    )
    (net (code "242") (name "Net-(RGB13-GREEN_CATHODE)") (class "Default")
      (node (ref "R39") (pin "2") (pinfunction "2_2") (pintype "passive"))
      (node (ref "RGB13") (pin "G") (pinfunction "GREEN_CATHODE_G") (pintype "bidirectional"))
    )
    (net (code "243") (name "Net-(RGB13-RED_CATHODE)") (class "Default")
      (node (ref "R37") (pin "2") (pinfunction "2_2") (pintype "passive"))
      (node (ref "RGB13") (pin "R") (pinfunction "RED_CATHODE_R") (pintype "bidirectional"))
    )
    (net (code "244") (name "Net-(RGB14-BLUE_CATHODE)") (class "Default")
      (node (ref "R41") (pin "2") (pinfunction "2_2") (pintype "passive"))
      (node (ref "RGB14") (pin "B") (pinfunction "BLUE_CATHODE_B") (pintype "bidirectional"))
    )
    (net (code "245") (name "Net-(RGB14-GREEN_CATHODE)") (class "Default")
      (node (ref "R42") (pin "2") (pinfunction "2_2") (pintype "passive"))
      (node (ref "RGB14") (pin "G") (pinfunction "GREEN_CATHODE_G") (pintype "bidirectional"))
    )
    (net (code "246") (name "Net-(RGB14-RED_CATHODE)") (class "Default")
      (node (ref "R40") (pin "2") (pinfunction "2_2") (pintype "passive"))
      (node (ref "RGB14") (pin "R") (pinfunction "RED_CATHODE_R") (pintype "bidirectional"))
    )
    (net (code "247") (name "Net-(RGB15-BLUE_CATHODE)") (class "Default")
      (node (ref "R44") (pin "2") (pinfunction "2_2") (pintype "passive"))
      (node (ref "RGB15") (pin "B") (pinfunction "BLUE_CATHODE_B") (pintype "bidirectional"))
    )
    (net (code "248") (name "Net-(RGB15-GREEN_CATHODE)") (class "Default")
      (node (ref "R45") (pin "2") (pinfunction "2_2") (pintype "passive"))
      (node (ref "RGB15") (pin "G") (pinfunction "GREEN_CATHODE_G") (pintype "bidirectional"))
    )
    (net (code "249") (name "Net-(RGB15-RED_CATHODE)") (class "Default")
      (node (ref "R43") (pin "2") (pinfunction "2_2") (pintype "passive"))
      (node (ref "RGB15") (pin "R") (pinfunction "RED_CATHODE_R") (pintype "bidirectional"))
    )
    (net (code "250") (name "Net-(RGB16-BLUE_CATHODE)") (class "Default")
      (node (ref "R47") (pin "2") (pinfunction "2_2") (pintype "passive"))
      (node (ref "RGB16") (pin "B") (pinfunction "BLUE_CATHODE_B") (pintype "bidirectional"))
    )
    (net (code "251") (name "Net-(RGB16-GREEN_CATHODE)") (class "Default")
      (node (ref "R48") (pin "2") (pinfunction "2_2") (pintype "passive"))
      (node (ref "RGB16") (pin "G") (pinfunction "GREEN_CATHODE_G") (pintype "bidirectional"))
    )
    (net (code "252") (name "Net-(RGB16-RED_CATHODE)") (class "Default")
      (node (ref "R46") (pin "2") (pinfunction "2_2") (pintype "passive"))
      (node (ref "RGB16") (pin "R") (pinfunction "RED_CATHODE_R") (pintype "bidirectional"))
    )
    (net (code "253") (name "Net-(RGB17-BLUE_CATHODE)") (class "Default")
      (node (ref "R50") (pin "2") (pinfunction "2_2") (pintype "passive"))
      (node (ref "RGB17") (pin "B") (pinfunction "BLUE_CATHODE_B") (pintype "bidirectional"))
    )
    (net (code "254") (name "Net-(RGB17-GREEN_CATHODE)") (class "Default")
      (node (ref "R51") (pin "2") (pinfunction "2_2") (pintype "passive"))
      (node (ref "RGB17") (pin "G") (pinfunction "GREEN_CATHODE_G") (pintype "bidirectional"))
    )
    (net (code "255") (name "Net-(RGB17-RED_CATHODE)") (class "Default")
      (node (ref "R49") (pin "2") (pinfunction "2_2") (pintype "passive"))
      (node (ref "RGB17") (pin "R") (pinfunction "RED_CATHODE_R") (pintype "bidirectional"))
    )
    (net (code "256") (name "Net-(RGB18-BLUE_CATHODE)") (class "Default")
      (node (ref "R53") (pin "2") (pinfunction "2_2") (pintype "passive"))
      (node (ref "RGB18") (pin "B") (pinfunction "BLUE_CATHODE_B") (pintype "bidirectional"))
    )
    (net (code "257") (name "Net-(RGB18-GREEN_CATHODE)") (class "Default")
      (node (ref "R54") (pin "2") (pinfunction "2_2") (pintype "passive"))
      (node (ref "RGB18") (pin "G") (pinfunction "GREEN_CATHODE_G") (pintype "bidirectional"))
    )
    (net (code "258") (name "Net-(RGB18-RED_CATHODE)") (class "Default")
      (node (ref "R52") (pin "2") (pinfunction "2_2") (pintype "passive"))
      (node (ref "RGB18") (pin "R") (pinfunction "RED_CATHODE_R") (pintype "bidirectional"))
    )
    (net (code "259") (name "Net-(RGB19-BLUE_CATHODE)") (class "Default")
      (node (ref "R56") (pin "2") (pinfunction "2_2") (pintype "passive"))
      (node (ref "RGB19") (pin "B") (pinfunction "BLUE_CATHODE_B") (pintype "bidirectional"))
    )
    (net (code "260") (name "Net-(RGB19-GREEN_CATHODE)") (class "Default")
      (node (ref "R57") (pin "2") (pinfunction "2_2") (pintype "passive"))
      (node (ref "RGB19") (pin "G") (pinfunction "GREEN_CATHODE_G") (pintype "bidirectional"))
    )
    (net (code "261") (name "Net-(RGB19-RED_CATHODE)") (class "Default")
      (node (ref "R55") (pin "2") (pinfunction "2_2") (pintype "passive"))
      (node (ref "RGB19") (pin "R") (pinfunction "RED_CATHODE_R") (pintype "bidirectional"))
    )
    (net (code "262") (name "Net-(RGB20-BLUE_CATHODE)") (class "Default")
      (node (ref "R59") (pin "2") (pinfunction "2_2") (pintype "passive"))
      (node (ref "RGB20") (pin "B") (pinfunction "BLUE_CATHODE_B") (pintype "bidirectional"))
    )
    (net (code "263") (name "Net-(RGB20-GREEN_CATHODE)") (class "Default")
      (node (ref "R60") (pin "2") (pinfunction "2_2") (pintype "passive"))
      (node (ref "RGB20") (pin "G") (pinfunction "GREEN_CATHODE_G") (pintype "bidirectional"))
    )
    (net (code "264") (name "Net-(RGB20-RED_CATHODE)") (class "Default")
      (node (ref "R58") (pin "2") (pinfunction "2_2") (pintype "passive"))
      (node (ref "RGB20") (pin "R") (pinfunction "RED_CATHODE_R") (pintype "bidirectional"))
    )
    (net (code "265") (name "Net-(RGB21-BLUE_CATHODE)") (class "Default")
      (node (ref "R62") (pin "2") (pinfunction "2_2") (pintype "passive"))
      (node (ref "RGB21") (pin "B") (pinfunction "BLUE_CATHODE_B") (pintype "bidirectional"))
    )
    (net (code "266") (name "Net-(RGB21-GREEN_CATHODE)") (class "Default")
      (node (ref "R63") (pin "2") (pinfunction "2_2") (pintype "passive"))
      (node (ref "RGB21") (pin "G") (pinfunction "GREEN_CATHODE_G") (pintype "bidirectional"))
    )
    (net (code "267") (name "Net-(RGB21-RED_CATHODE)") (class "Default")
      (node (ref "R61") (pin "2") (pinfunction "2_2") (pintype "passive"))
      (node (ref "RGB21") (pin "R") (pinfunction "RED_CATHODE_R") (pintype "bidirectional"))
    )
    (net (code "268") (name "Net-(RGB22-BLUE_CATHODE)") (class "Default")
      (node (ref "R65") (pin "2") (pinfunction "2_2") (pintype "passive"))
      (node (ref "RGB22") (pin "B") (pinfunction "BLUE_CATHODE_B") (pintype "bidirectional"))
    )
    (net (code "269") (name "Net-(RGB22-GREEN_CATHODE)") (class "Default")
      (node (ref "R66") (pin "2") (pinfunction "2_2") (pintype "passive"))
      (node (ref "RGB22") (pin "G") (pinfunction "GREEN_CATHODE_G") (pintype "bidirectional"))
    )
    (net (code "270") (name "Net-(RGB22-RED_CATHODE)") (class "Default")
      (node (ref "R64") (pin "2") (pinfunction "2_2") (pintype "passive"))
      (node (ref "RGB22") (pin "R") (pinfunction "RED_CATHODE_R") (pintype "bidirectional"))
    )
    (net (code "271") (name "Net-(RGB23-BLUE_CATHODE)") (class "Default")
      (node (ref "R68") (pin "2") (pinfunction "2_2") (pintype "passive"))
      (node (ref "RGB23") (pin "B") (pinfunction "BLUE_CATHODE_B") (pintype "bidirectional"))
    )
    (net (code "272") (name "Net-(RGB23-GREEN_CATHODE)") (class "Default")
      (node (ref "R69") (pin "2") (pinfunction "2_2") (pintype "passive"))
      (node (ref "RGB23") (pin "G") (pinfunction "GREEN_CATHODE_G") (pintype "bidirectional"))
    )
    (net (code "273") (name "Net-(RGB23-RED_CATHODE)") (class "Default")
      (node (ref "R67") (pin "2") (pinfunction "2_2") (pintype "passive"))
      (node (ref "RGB23") (pin "R") (pinfunction "RED_CATHODE_R") (pintype "bidirectional"))
    )
    (net (code "274") (name "Net-(RGB24-BLUE_CATHODE)") (class "Default")
      (node (ref "R71") (pin "2") (pinfunction "2_2") (pintype "passive"))
      (node (ref "RGB24") (pin "B") (pinfunction "BLUE_CATHODE_B") (pintype "bidirectional"))
    )
    (net (code "275") (name "Net-(RGB24-GREEN_CATHODE)") (class "Default")
      (node (ref "R72") (pin "2") (pinfunction "2_2") (pintype "passive"))
      (node (ref "RGB24") (pin "G") (pinfunction "GREEN_CATHODE_G") (pintype "bidirectional"))
    )
    (net (code "276") (name "Net-(RGB24-RED_CATHODE)") (class "Default")
      (node (ref "R70") (pin "2") (pinfunction "2_2") (pintype "passive"))
      (node (ref "RGB24") (pin "R") (pinfunction "RED_CATHODE_R") (pintype "bidirectional"))
    )
    (net (code "277") (name "Net-(RGB25-BLUE_CATHODE)") (class "Default")
      (node (ref "R74") (pin "2") (pinfunction "2_2") (pintype "passive"))
      (node (ref "RGB25") (pin "B") (pinfunction "BLUE_CATHODE_B") (pintype "bidirectional"))
    )
    (net (code "278") (name "Net-(RGB25-GREEN_CATHODE)") (class "Default")
      (node (ref "R75") (pin "2") (pinfunction "2_2") (pintype "passive"))
      (node (ref "RGB25") (pin "G") (pinfunction "GREEN_CATHODE_G") (pintype "bidirectional"))
    )
    (net (code "279") (name "Net-(RGB25-RED_CATHODE)") (class "Default")
      (node (ref "R73") (pin "2") (pinfunction "2_2") (pintype "passive"))
      (node (ref "RGB25") (pin "R") (pinfunction "RED_CATHODE_R") (pintype "bidirectional"))
    )
    (net (code "280") (name "Net-(RGB26-BLUE_CATHODE)") (class "Default")
      (node (ref "R77") (pin "2") (pinfunction "2_2") (pintype "passive"))
      (node (ref "RGB26") (pin "B") (pinfunction "BLUE_CATHODE_B") (pintype "bidirectional"))
    )
    (net (code "281") (name "Net-(RGB26-GREEN_CATHODE)") (class "Default")
      (node (ref "R78") (pin "2") (pinfunction "2_2") (pintype "passive"))
      (node (ref "RGB26") (pin "G") (pinfunction "GREEN_CATHODE_G") (pintype "bidirectional"))
    )
    (net (code "282") (name "Net-(RGB26-RED_CATHODE)") (class "Default")
      (node (ref "R76") (pin "2") (pinfunction "2_2") (pintype "passive"))
      (node (ref "RGB26") (pin "R") (pinfunction "RED_CATHODE_R") (pintype "bidirectional"))
    )
    (net (code "283") (name "Net-(RGB27-BLUE_CATHODE)") (class "Default")
      (node (ref "R80") (pin "2") (pinfunction "2_2") (pintype "passive"))
      (node (ref "RGB27") (pin "B") (pinfunction "BLUE_CATHODE_B") (pintype "bidirectional"))
    )
    (net (code "284") (name "Net-(RGB27-GREEN_CATHODE)") (class "Default")
      (node (ref "R81") (pin "2") (pinfunction "2_2") (pintype "passive"))
      (node (ref "RGB27") (pin "G") (pinfunction "GREEN_CATHODE_G") (pintype "bidirectional"))
    )
    (net (code "285") (name "Net-(RGB27-RED_CATHODE)") (class "Default")
      (node (ref "R79") (pin "2") (pinfunction "2_2") (pintype "passive"))
      (node (ref "RGB27") (pin "R") (pinfunction "RED_CATHODE_R") (pintype "bidirectional"))
    )
    (net (code "286") (name "Net-(RGB28-BLUE_CATHODE)") (class "Default")
      (node (ref "R83") (pin "2") (pinfunction "2_2") (pintype "passive"))
      (node (ref "RGB28") (pin "B") (pinfunction "BLUE_CATHODE_B") (pintype "bidirectional"))
    )
    (net (code "287") (name "Net-(RGB28-GREEN_CATHODE)") (class "Default")
      (node (ref "R84") (pin "2") (pinfunction "2_2") (pintype "passive"))
      (node (ref "RGB28") (pin "G") (pinfunction "GREEN_CATHODE_G") (pintype "bidirectional"))
    )
    (net (code "288") (name "Net-(RGB28-RED_CATHODE)") (class "Default")
      (node (ref "R82") (pin "2") (pinfunction "2_2") (pintype "passive"))
      (node (ref "RGB28") (pin "R") (pinfunction "RED_CATHODE_R") (pintype "bidirectional"))
    )
    (net (code "289") (name "Net-(RGB29-BLUE_CATHODE)") (class "Default")
      (node (ref "R86") (pin "2") (pinfunction "2_2") (pintype "passive"))
      (node (ref "RGB29") (pin "B") (pinfunction "BLUE_CATHODE_B") (pintype "bidirectional"))
    )
    (net (code "290") (name "Net-(RGB29-GREEN_CATHODE)") (class "Default")
      (node (ref "R87") (pin "2") (pinfunction "2_2") (pintype "passive"))
      (node (ref "RGB29") (pin "G") (pinfunction "GREEN_CATHODE_G") (pintype "bidirectional"))
    )
    (net (code "291") (name "Net-(RGB29-RED_CATHODE)") (class "Default")
      (node (ref "R85") (pin "2") (pinfunction "2_2") (pintype "passive"))
      (node (ref "RGB29") (pin "R") (pinfunction "RED_CATHODE_R") (pintype "bidirectional"))
    )
    (net (code "292") (name "Net-(RGB30-BLUE_CATHODE)") (class "Default")
      (node (ref "R89") (pin "2") (pinfunction "2_2") (pintype "passive"))
      (node (ref "RGB30") (pin "B") (pinfunction "BLUE_CATHODE_B") (pintype "bidirectional"))
    )
    (net (code "293") (name "Net-(RGB30-GREEN_CATHODE)") (class "Default")
      (node (ref "R90") (pin "2") (pinfunction "2_2") (pintype "passive"))
      (node (ref "RGB30") (pin "G") (pinfunction "GREEN_CATHODE_G") (pintype "bidirectional"))
    )
    (net (code "294") (name "Net-(RGB30-RED_CATHODE)") (class "Default")
      (node (ref "R88") (pin "2") (pinfunction "2_2") (pintype "passive"))
      (node (ref "RGB30") (pin "R") (pinfunction "RED_CATHODE_R") (pintype "bidirectional"))
    )
    (net (code "295") (name "Net-(RGB31-BLUE_CATHODE)") (class "Default")
      (node (ref "R92") (pin "2") (pinfunction "2_2") (pintype "passive"))
      (node (ref "RGB31") (pin "B") (pinfunction "BLUE_CATHODE_B") (pintype "bidirectional"))
    )
    (net (code "296") (name "Net-(RGB31-GREEN_CATHODE)") (class "Default")
      (node (ref "R93") (pin "2") (pinfunction "2_2") (pintype "passive"))
      (node (ref "RGB31") (pin "G") (pinfunction "GREEN_CATHODE_G") (pintype "bidirectional"))
    )
    (net (code "297") (name "Net-(RGB31-RED_CATHODE)") (class "Default")
      (node (ref "R91") (pin "2") (pinfunction "2_2") (pintype "passive"))
      (node (ref "RGB31") (pin "R") (pinfunction "RED_CATHODE_R") (pintype "bidirectional"))
    )
    (net (code "298") (name "Net-(RGB32-BLUE_CATHODE)") (class "Default")
      (node (ref "R95") (pin "2") (pinfunction "2_2") (pintype "passive"))
      (node (ref "RGB32") (pin "B") (pinfunction "BLUE_CATHODE_B") (pintype "bidirectional"))
    )
    (net (code "299") (name "Net-(RGB32-GREEN_CATHODE)") (class "Default")
      (node (ref "R96") (pin "2") (pinfunction "2_2") (pintype "passive"))
      (node (ref "RGB32") (pin "G") (pinfunction "GREEN_CATHODE_G") (pintype "bidirectional"))
    )
    (net (code "300") (name "Net-(RGB32-RED_CATHODE)") (class "Default")
      (node (ref "R94") (pin "2") (pinfunction "2_2") (pintype "passive"))
      (node (ref "RGB32") (pin "R") (pinfunction "RED_CATHODE_R") (pintype "bidirectional"))
    )
    (net (code "301") (name "Net-(RGB33-BLUE_CATHODE)") (class "Default")
      (node (ref "R98") (pin "2") (pinfunction "2_2") (pintype "passive"))
      (node (ref "RGB33") (pin "B") (pinfunction "BLUE_CATHODE_B") (pintype "bidirectional"))
    )
    (net (code "302") (name "Net-(RGB33-GREEN_CATHODE)") (class "Default")
      (node (ref "R99") (pin "2") (pinfunction "2_2") (pintype "passive"))
      (node (ref "RGB33") (pin "G") (pinfunction "GREEN_CATHODE_G") (pintype "bidirectional"))
    )
    (net (code "303") (name "Net-(RGB33-RED_CATHODE)") (class "Default")
      (node (ref "R97") (pin "2") (pinfunction "2_2") (pintype "passive"))
      (node (ref "RGB33") (pin "R") (pinfunction "RED_CATHODE_R") (pintype "bidirectional"))
    )
    (net (code "304") (name "Net-(RGB34-BLUE_CATHODE)") (class "Default")
      (node (ref "R101") (pin "2") (pinfunction "2_2") (pintype "passive"))
      (node (ref "RGB34") (pin "B") (pinfunction "BLUE_CATHODE_B") (pintype "bidirectional"))
    )
    (net (code "305") (name "Net-(RGB34-GREEN_CATHODE)") (class "Default")
      (node (ref "R102") (pin "2") (pinfunction "2_2") (pintype "passive"))
      (node (ref "RGB34") (pin "G") (pinfunction "GREEN_CATHODE_G") (pintype "bidirectional"))
    )
    (net (code "306") (name "Net-(RGB34-RED_CATHODE)") (class "Default")
      (node (ref "R100") (pin "2") (pinfunction "2_2") (pintype "passive"))
      (node (ref "RGB34") (pin "R") (pinfunction "RED_CATHODE_R") (pintype "bidirectional"))
    )
    (net (code "307") (name "Net-(RGB35-BLUE_CATHODE)") (class "Default")
      (node (ref "R104") (pin "2") (pinfunction "2_2") (pintype "passive"))
      (node (ref "RGB35") (pin "B") (pinfunction "BLUE_CATHODE_B") (pintype "bidirectional"))
    )
    (net (code "308") (name "Net-(RGB35-GREEN_CATHODE)") (class "Default")
      (node (ref "R105") (pin "2") (pinfunction "2_2") (pintype "passive"))
      (node (ref "RGB35") (pin "G") (pinfunction "GREEN_CATHODE_G") (pintype "bidirectional"))
    )
    (net (code "309") (name "Net-(RGB35-RED_CATHODE)") (class "Default")
      (node (ref "R103") (pin "2") (pinfunction "2_2") (pintype "passive"))
      (node (ref "RGB35") (pin "R") (pinfunction "RED_CATHODE_R") (pintype "bidirectional"))
    )
    (net (code "310") (name "Net-(RGB36-BLUE_CATHODE)") (class "Default")
      (node (ref "R107") (pin "2") (pinfunction "2_2") (pintype "passive"))
      (node (ref "RGB36") (pin "B") (pinfunction "BLUE_CATHODE_B") (pintype "bidirectional"))
    )
    (net (code "311") (name "Net-(RGB36-GREEN_CATHODE)") (class "Default")
      (node (ref "R108") (pin "2") (pinfunction "2_2") (pintype "passive"))
      (node (ref "RGB36") (pin "G") (pinfunction "GREEN_CATHODE_G") (pintype "bidirectional"))
    )
    (net (code "312") (name "Net-(RGB36-RED_CATHODE)") (class "Default")
      (node (ref "R106") (pin "2") (pinfunction "2_2") (pintype "passive"))
      (node (ref "RGB36") (pin "R") (pinfunction "RED_CATHODE_R") (pintype "bidirectional"))
    )
    (net (code "313") (name "P9") (class "Default")
      (node (ref "CON2") (pin "P$9") (pinfunction "9_P$9") (pintype "passive"))
    )
    (net (code "314") (name "P11") (class "Default")
      (node (ref "CON2") (pin "P$11") (pinfunction "11_P$11") (pintype "passive"))
    )
    (net (code "315") (name "P12") (class "Default")
      (node (ref "CON2") (pin "P$12") (pinfunction "12_P$12") (pintype "passive"))
    )
    (net (code "316") (name "P14") (class "Default")
      (node (ref "CON2") (pin "P$14") (pinfunction "14_P$14") (pintype "passive"))
    )
    (net (code "317") (name "P15") (class "Default")
      (node (ref "CON2") (pin "P$15") (pinfunction "15_P$15") (pintype "passive"))
    )
    (net (code "318") (name "P17") (class "Default")
      (node (ref "CON2") (pin "P$17") (pinfunction "17_P$17") (pintype "passive"))
    )
    (net (code "319") (name "P18") (class "Default")
      (node (ref "CON2") (pin "P$18") (pinfunction "18_P$18") (pintype "passive"))
    )
    (net (code "320") (name "P20") (class "Default")
      (node (ref "CON2") (pin "P$20") (pinfunction "20_P$20") (pintype "passive"))
    )
    (net (code "321") (name "P21") (class "Default")
      (node (ref "CON2") (pin "P$21") (pinfunction "21_P$21") (pintype "passive"))
    )
    (net (code "322") (name "P23") (class "Default")
      (node (ref "CON2") (pin "P$23") (pinfunction "23_P$23") (pintype "passive"))
    )
    (net (code "323") (name "P24") (class "Default")
      (node (ref "CON2") (pin "P$24") (pinfunction "24_P$24") (pintype "passive"))
    )
    (net (code "324") (name "P26") (class "Default")
      (node (ref "CON2") (pin "P$26") (pinfunction "26_P$26") (pintype "passive"))
    )
    (net (code "325") (name "P80") (class "Default")
      (node (ref "CON1") (pin "P$80") (pinfunction "80_P$80") (pintype "passive"))
    )
    (net (code "326") (name "P82") (class "Default")
      (node (ref "CON1") (pin "P$82") (pinfunction "82_P$82") (pintype "passive"))
    )
    (net (code "327") (name "P83") (class "Default")
      (node (ref "CON1") (pin "P$83") (pinfunction "83_P$83") (pintype "passive"))
    )
    (net (code "328") (name "P85") (class "Default")
      (node (ref "CON1") (pin "P$85") (pinfunction "85_P$85") (pintype "passive"))
    )
    (net (code "329") (name "P86") (class "Default")
      (node (ref "CON1") (pin "P$86") (pinfunction "86_P$86") (pintype "passive"))
    )
    (net (code "330") (name "P88") (class "Default")
      (node (ref "CON1") (pin "P$88") (pinfunction "88_P$88") (pintype "passive"))
    )
    (net (code "331") (name "P89") (class "Default")
      (node (ref "CON1") (pin "P$89") (pinfunction "89_P$89") (pintype "passive"))
    )
    (net (code "332") (name "P91") (class "Default")
      (node (ref "CON1") (pin "P$91") (pinfunction "91_P$91") (pintype "passive"))
    )
    (net (code "333") (name "P92") (class "Default")
      (node (ref "CON1") (pin "P$92") (pinfunction "92_P$92") (pintype "passive"))
    )
    (net (code "334") (name "P94") (class "Default")
      (node (ref "CON1") (pin "P$94") (pinfunction "94_P$94") (pintype "passive"))
    )
    (net (code "335") (name "P95") (class "Default")
      (node (ref "CON1") (pin "P$95") (pinfunction "95_P$95") (pintype "passive"))
    )
    (net (code "336") (name "P97") (class "Default")
      (node (ref "CON1") (pin "P$97") (pinfunction "97_P$97") (pintype "passive"))
    )
    (net (code "337") (name "P98") (class "Default")
      (node (ref "CON1") (pin "P$98") (pinfunction "98_P$98") (pintype "passive"))
    )
    (net (code "338") (name "P100") (class "Default")
      (node (ref "CON1") (pin "P$100") (pinfunction "100_P$100") (pintype "passive"))
    )
    (net (code "339") (name "P101") (class "Default")
      (node (ref "CON1") (pin "P$101") (pinfunction "101_P$101") (pintype "passive"))
    )
    (net (code "340") (name "P103") (class "Default")
      (node (ref "CON1") (pin "P$103") (pinfunction "103_P$103") (pintype "passive"))
    )
    (net (code "341") (name "P104") (class "Default")
      (node (ref "CON1") (pin "P$104") (pinfunction "104_P$104") (pintype "passive"))
    )
    (net (code "342") (name "R1") (class "Default")
      (node (ref "CON1") (pin "P$2") (pinfunction "2_P$2") (pintype "passive"))
      (node (ref "ULN1") (pin "1") (pinfunction "1_1") (pintype "bidirectional"))
    )
    (net (code "343") (name "R2") (class "Default")
      (node (ref "CON1") (pin "P$6") (pinfunction "6_P$6") (pintype "passive"))
      (node (ref "ULN1") (pin "4") (pinfunction "4_4") (pintype "bidirectional"))
    )
    (net (code "344") (name "R3") (class "Default")
      (node (ref "CON1") (pin "P$11") (pinfunction "11_P$11") (pintype "passive"))
      (node (ref "ULN1") (pin "7") (pinfunction "7_7") (pintype "bidirectional"))
    )
    (net (code "345") (name "R4") (class "Default")
      (node (ref "CON1") (pin "P$15") (pinfunction "15_P$15") (pintype "passive"))
      (node (ref "ULN2") (pin "2") (pinfunction "2_2") (pintype "bidirectional"))
    )
    (net (code "346") (name "R5") (class "Default")
      (node (ref "CON1") (pin "P$20") (pinfunction "20_P$20") (pintype "passive"))
      (node (ref "ULN2") (pin "5") (pinfunction "5_5") (pintype "bidirectional"))
    )
    (net (code "347") (name "R6") (class "Default")
      (node (ref "CON1") (pin "P$24") (pinfunction "24_P$24") (pintype "passive"))
      (node (ref "ULN2") (pin "8") (pinfunction "8_8") (pintype "bidirectional"))
    )
    (net (code "348") (name "R7") (class "Default")
      (node (ref "CON1") (pin "P$29") (pinfunction "29_P$29") (pintype "passive"))
      (node (ref "ULN3") (pin "3") (pinfunction "3_3") (pintype "bidirectional"))
    )
    (net (code "349") (name "R8") (class "Default")
      (node (ref "CON1") (pin "P$33") (pinfunction "33_P$33") (pintype "passive"))
      (node (ref "ULN3") (pin "6") (pinfunction "6_6") (pintype "bidirectional"))
    )
    (net (code "350") (name "R9") (class "Default")
      (node (ref "CON1") (pin "P$38") (pinfunction "38_P$38") (pintype "passive"))
      (node (ref "ULN4") (pin "1") (pinfunction "1_1") (pintype "bidirectional"))
    )
    (net (code "351") (name "R10") (class "Default")
      (node (ref "CON1") (pin "P$42") (pinfunction "42_P$42") (pintype "passive"))
      (node (ref "ULN4") (pin "4") (pinfunction "4_4") (pintype "bidirectional"))
    )
    (net (code "352") (name "R11") (class "Default")
      (node (ref "CON1") (pin "P$47") (pinfunction "47_P$47") (pintype "passive"))
      (node (ref "ULN4") (pin "7") (pinfunction "7_7") (pintype "bidirectional"))
    )
    (net (code "353") (name "R12") (class "Default")
      (node (ref "CON1") (pin "P$51") (pinfunction "51_P$51") (pintype "passive"))
      (node (ref "ULN5") (pin "2") (pinfunction "2_2") (pintype "bidirectional"))
    )
    (net (code "354") (name "R13") (class "Default")
      (node (ref "CON1") (pin "P$56") (pinfunction "56_P$56") (pintype "passive"))
      (node (ref "ULN5") (pin "5") (pinfunction "5_5") (pintype "bidirectional"))
    )
    (net (code "355") (name "R14") (class "Default")
      (node (ref "CON1") (pin "P$60") (pinfunction "60_P$60") (pintype "passive"))
      (node (ref "ULN5") (pin "8") (pinfunction "8_8") (pintype "bidirectional"))
    )
    (net (code "356") (name "R15") (class "Default")
      (node (ref "CON1") (pin "P$65") (pinfunction "65_P$65") (pintype "passive"))
      (node (ref "ULN6") (pin "3") (pinfunction "3_3") (pintype "bidirectional"))
    )
    (net (code "357") (name "R16") (class "Default")
      (node (ref "CON1") (pin "P$133") (pinfunction "133_P$133") (pintype "passive"))
      (node (ref "ULN6") (pin "6") (pinfunction "6_6") (pintype "bidirectional"))
    )
    (net (code "358") (name "R17") (class "Default")
      (node (ref "CON1") (pin "P$125") (pinfunction "125_P$125") (pintype "passive"))
      (node (ref "ULN7") (pin "1") (pinfunction "1_1") (pintype "bidirectional"))
    )
    (net (code "359") (name "R18") (class "Default")
      (node (ref "CON1") (pin "P$119") (pinfunction "119_P$119") (pintype "passive"))
      (node (ref "ULN7") (pin "4") (pinfunction "4_4") (pintype "bidirectional"))
    )
    (net (code "360") (name "R19") (class "Default")
      (node (ref "CON1") (pin "P$115") (pinfunction "115_P$115") (pintype "passive"))
      (node (ref "ULN7") (pin "7") (pinfunction "7_7") (pintype "bidirectional"))
    )
    (net (code "361") (name "R20") (class "Default")
      (node (ref "CON2") (pin "P$6") (pinfunction "6_P$6") (pintype "passive"))
      (node (ref "ULN8") (pin "2") (pinfunction "2_2") (pintype "bidirectional"))
    )
    (net (code "362") (name "R21") (class "Default")
      (node (ref "CON2") (pin "P$2") (pinfunction "2_P$2") (pintype "passive"))
      (node (ref "ULN8") (pin "5") (pinfunction "5_5") (pintype "bidirectional"))
    )
    (net (code "363") (name "R22") (class "Default")
      (node (ref "CON2") (pin "P$74") (pinfunction "74_P$74") (pintype "passive"))
      (node (ref "ULN8") (pin "8") (pinfunction "8_8") (pintype "bidirectional"))
    )
    (net (code "364") (name "R23") (class "Default")
      (node (ref "CON2") (pin "P$79") (pinfunction "79_P$79") (pintype "passive"))
      (node (ref "ULN9") (pin "3") (pinfunction "3_3") (pintype "bidirectional"))
    )
    (net (code "365") (name "R24") (class "Default")
      (node (ref "CON2") (pin "P$83") (pinfunction "83_P$83") (pintype "passive"))
      (node (ref "ULN9") (pin "6") (pinfunction "6_6") (pintype "bidirectional"))
    )
    (net (code "366") (name "R25") (class "Default")
      (node (ref "CON2") (pin "P$88") (pinfunction "88_P$88") (pintype "passive"))
      (node (ref "ULN10") (pin "1") (pinfunction "1_1") (pintype "bidirectional"))
    )
    (net (code "367") (name "R26") (class "Default")
      (node (ref "CON2") (pin "P$92") (pinfunction "92_P$92") (pintype "passive"))
      (node (ref "ULN10") (pin "4") (pinfunction "4_4") (pintype "bidirectional"))
    )
    (net (code "368") (name "R27") (class "Default")
      (node (ref "CON2") (pin "P$97") (pinfunction "97_P$97") (pintype "passive"))
      (node (ref "ULN10") (pin "7") (pinfunction "7_7") (pintype "bidirectional"))
    )
    (net (code "369") (name "R28") (class "Default")
      (node (ref "CON2") (pin "P$101") (pinfunction "101_P$101") (pintype "passive"))
      (node (ref "ULN11") (pin "2") (pinfunction "2_2") (pintype "bidirectional"))
    )
    (net (code "370") (name "R29") (class "Default")
      (node (ref "CON2") (pin "P$106") (pinfunction "106_P$106") (pintype "passive"))
      (node (ref "ULN11") (pin "5") (pinfunction "5_5") (pintype "bidirectional"))
    )
    (net (code "371") (name "R30") (class "Default")
      (node (ref "CON2") (pin "P$110") (pinfunction "110_P$110") (pintype "passive"))
      (node (ref "ULN11") (pin "8") (pinfunction "8_8") (pintype "bidirectional"))
    )
    (net (code "372") (name "R31") (class "Default")
      (node (ref "CON2") (pin "P$115") (pinfunction "115_P$115") (pintype "passive"))
      (node (ref "ULN12") (pin "3") (pinfunction "3_3") (pintype "bidirectional"))
    )
    (net (code "373") (name "R32") (class "Default")
      (node (ref "CON2") (pin "P$119") (pinfunction "119_P$119") (pintype "passive"))
      (node (ref "ULN12") (pin "6") (pinfunction "6_6") (pintype "bidirectional"))
    )
    (net (code "374") (name "R33") (class "Default")
      (node (ref "CON2") (pin "P$124") (pinfunction "124_P$124") (pintype "passive"))
      (node (ref "ULN13") (pin "1") (pinfunction "1_1") (pintype "bidirectional"))
    )
    (net (code "375") (name "R34") (class "Default")
      (node (ref "CON2") (pin "P$128") (pinfunction "128_P$128") (pintype "passive"))
      (node (ref "ULN13") (pin "4") (pinfunction "4_4") (pintype "bidirectional"))
    )
    (net (code "376") (name "R35") (class "Default")
      (node (ref "CON2") (pin "P$133") (pinfunction "133_P$133") (pintype "passive"))
      (node (ref "ULN13") (pin "7") (pinfunction "7_7") (pintype "bidirectional"))
    )
    (net (code "377") (name "R36") (class "Default")
      (node (ref "CON2") (pin "P$137") (pinfunction "137_P$137") (pintype "passive"))
      (node (ref "ULN14") (pin "2") (pinfunction "2_2") (pintype "bidirectional"))
    )
    (net (code "378") (name "unconnected-(CON1-68-PadP$68)") (class "Default")
      (node (ref "CON1") (pin "P$68") (pinfunction "68_P$68") (pintype "passive"))
    )
    (net (code "379") (name "unconnected-(CON1-69-PadP$69)") (class "Default")
      (node (ref "CON1") (pin "P$69") (pinfunction "69_P$69") (pintype "passive"))
    )
    (net (code "380") (name "unconnected-(CON1-106-PadP$106)") (class "Default")
      (node (ref "CON1") (pin "P$106") (pinfunction "106_P$106") (pintype "passive"))
    )
    (net (code "381") (name "unconnected-(CON1-107-PadP$107)") (class "Default")
      (node (ref "CON1") (pin "P$107") (pinfunction "107_P$107") (pintype "passive"))
    )
    (net (code "382") (name "unconnected-(CON1-109-PadP$109)") (class "Default")
      (node (ref "CON1") (pin "P$109") (pinfunction "109_P$109") (pintype "passive"))
    )
    (net (code "383") (name "unconnected-(CON1-110-PadP$110)") (class "Default")
      (node (ref "CON1") (pin "P$110") (pinfunction "110_P$110") (pintype "passive"))
    )
    (net (code "384") (name "unconnected-(CON1-112-PadP$112)") (class "Default")
      (node (ref "CON1") (pin "P$112") (pinfunction "112_P$112") (pintype "passive"))
    )
    (net (code "385") (name "unconnected-(CON1-121-PadP$121)") (class "Default")
      (node (ref "CON1") (pin "P$121") (pinfunction "121_P$121") (pintype "passive"))
    )
    (net (code "386") (name "unconnected-(CON1-127-PadP$127)") (class "Default")
      (node (ref "CON1") (pin "P$127") (pinfunction "127_P$127") (pintype "passive"))
    )
    (net (code "387") (name "unconnected-(CON1-130-PadP$130)") (class "Default")
      (node (ref "CON1") (pin "P$130") (pinfunction "130_P$130") (pintype "passive"))
    )
    (net (code "388") (name "unconnected-(CON1-136-PadP$136)") (class "Default")
      (node (ref "CON1") (pin "P$136") (pinfunction "136_P$136") (pintype "passive"))
    )
    (net (code "389") (name "unconnected-(CON1-137-PadP$137)") (class "Default")
      (node (ref "CON1") (pin "P$137") (pinfunction "137_P$137") (pintype "passive"))
    )
    (net (code "390") (name "unconnected-(CON1-139-PadP$139)") (class "Default")
      (node (ref "CON1") (pin "P$139") (pinfunction "139_P$139") (pintype "passive"))
    )
    (net (code "391") (name "unconnected-(CON1-140-PadP$140)") (class "Default")
      (node (ref "CON1") (pin "P$140") (pinfunction "140_P$140") (pintype "passive"))
    )
    (net (code "392") (name "unconnected-(CON2-27-PadP$27)") (class "Default")
      (node (ref "CON2") (pin "P$27") (pinfunction "27_P$27") (pintype "passive"))
    )
    (net (code "393") (name "unconnected-(CON2-29-PadP$29)") (class "Default")
      (node (ref "CON2") (pin "P$29") (pinfunction "29_P$29") (pintype "passive"))
    )
    (net (code "394") (name "unconnected-(CON2-30-PadP$30)") (class "Default")
      (node (ref "CON2") (pin "P$30") (pinfunction "30_P$30") (pintype "passive"))
    )
    (net (code "395") (name "unconnected-(CON2-32-PadP$32)") (class "Default")
      (node (ref "CON2") (pin "P$32") (pinfunction "32_P$32") (pintype "passive"))
    )
    (net (code "396") (name "unconnected-(CON2-33-PadP$33)") (class "Default")
      (node (ref "CON2") (pin "P$33") (pinfunction "33_P$33") (pintype "passive"))
    )
    (net (code "397") (name "unconnected-(CON2-35-PadP$35)") (class "Default")
      (node (ref "CON2") (pin "P$35") (pinfunction "35_P$35") (pintype "passive"))
    )
    (net (code "398") (name "unconnected-(CON2-36-PadP$36)") (class "Default")
      (node (ref "CON2") (pin "P$36") (pinfunction "36_P$36") (pintype "passive"))
    )
    (net (code "399") (name "unconnected-(CON2-38-PadP$38)") (class "Default")
      (node (ref "CON2") (pin "P$38") (pinfunction "38_P$38") (pintype "passive"))
    )
    (net (code "400") (name "unconnected-(CON2-39-PadP$39)") (class "Default")
      (node (ref "CON2") (pin "P$39") (pinfunction "39_P$39") (pintype "passive"))
    )
    (net (code "401") (name "unconnected-(CON2-41-PadP$41)") (class "Default")
      (node (ref "CON2") (pin "P$41") (pinfunction "41_P$41") (pintype "passive"))
    )
    (net (code "402") (name "unconnected-(CON2-42-PadP$42)") (class "Default")
      (node (ref "CON2") (pin "P$42") (pinfunction "42_P$42") (pintype "passive"))
    )
    (net (code "403") (name "unconnected-(CON2-44-PadP$44)") (class "Default")
      (node (ref "CON2") (pin "P$44") (pinfunction "44_P$44") (pintype "passive"))
    )
    (net (code "404") (name "unconnected-(CON2-45-PadP$45)") (class "Default")
      (node (ref "CON2") (pin "P$45") (pinfunction "45_P$45") (pintype "passive"))
    )
    (net (code "405") (name "unconnected-(CON2-47-PadP$47)") (class "Default")
      (node (ref "CON2") (pin "P$47") (pinfunction "47_P$47") (pintype "passive"))
    )
    (net (code "406") (name "unconnected-(CON2-48-PadP$48)") (class "Default")
      (node (ref "CON2") (pin "P$48") (pinfunction "48_P$48") (pintype "passive"))
    )
    (net (code "407") (name "unconnected-(CON2-50-PadP$50)") (class "Default")
      (node (ref "CON2") (pin "P$50") (pinfunction "50_P$50") (pintype "passive"))
    )
    (net (code "408") (name "unconnected-(CON2-51-PadP$51)") (class "Default")
      (node (ref "CON2") (pin "P$51") (pinfunction "51_P$51") (pintype "passive"))
    )
    (net (code "409") (name "unconnected-(CON2-53-PadP$53)") (class "Default")
      (node (ref "CON2") (pin "P$53") (pinfunction "53_P$53") (pintype "passive"))
    )
    (net (code "410") (name "unconnected-(CON2-54-PadP$54)") (class "Default")
      (node (ref "CON2") (pin "P$54") (pinfunction "54_P$54") (pintype "passive"))
    )
    (net (code "411") (name "unconnected-(CON2-56-PadP$56)") (class "Default")
      (node (ref "CON2") (pin "P$56") (pinfunction "56_P$56") (pintype "passive"))
    )
    (net (code "412") (name "unconnected-(CON2-57-PadP$57)") (class "Default")
      (node (ref "CON2") (pin "P$57") (pinfunction "57_P$57") (pintype "passive"))
    )
    (net (code "413") (name "unconnected-(CON2-59-PadP$59)") (class "Default")
      (node (ref "CON2") (pin "P$59") (pinfunction "59_P$59") (pintype "passive"))
    )
    (net (code "414") (name "unconnected-(CON2-60-PadP$60)") (class "Default")
      (node (ref "CON2") (pin "P$60") (pinfunction "60_P$60") (pintype "passive"))
    )
    (net (code "415") (name "unconnected-(CON2-62-PadP$62)") (class "Default")
      (node (ref "CON2") (pin "P$62") (pinfunction "62_P$62") (pintype "passive"))
    )
    (net (code "416") (name "unconnected-(CON2-63-PadP$63)") (class "Default")
      (node (ref "CON2") (pin "P$63") (pinfunction "63_P$63") (pintype "passive"))
    )
    (net (code "417") (name "unconnected-(CON2-65-PadP$65)") (class "Default")
      (node (ref "CON2") (pin "P$65") (pinfunction "65_P$65") (pintype "passive"))
    )
    (net (code "418") (name "unconnected-(CON2-66-PadP$66)") (class "Default")
      (node (ref "CON2") (pin "P$66") (pinfunction "66_P$66") (pintype "passive"))
    )
    (net (code "419") (name "unconnected-(CON2-68-PadP$68)") (class "Default")
      (node (ref "CON2") (pin "P$68") (pinfunction "68_P$68") (pintype "passive"))
    )
    (net (code "420") (name "unconnected-(CON2-69-PadP$69)") (class "Default")
      (node (ref "CON2") (pin "P$69") (pinfunction "69_P$69") (pintype "passive"))
    )
    (net (code "421") (name "unconnected-(ULN1-Pad10)") (class "Default")
      (node (ref "ULN1") (pin "10") (pinfunction "10_10") (pintype "bidirectional"))
    )
    (net (code "422") (name "unconnected-(ULN2-Pad10)") (class "Default")
      (node (ref "ULN2") (pin "10") (pinfunction "10_10") (pintype "bidirectional"))
    )
    (net (code "423") (name "unconnected-(ULN3-Pad10)") (class "Default")
      (node (ref "ULN3") (pin "10") (pinfunction "10_10") (pintype "bidirectional"))
    )
    (net (code "424") (name "unconnected-(ULN4-Pad10)") (class "Default")
      (node (ref "ULN4") (pin "10") (pinfunction "10_10") (pintype "bidirectional"))
    )
    (net (code "425") (name "unconnected-(ULN5-Pad10)") (class "Default")
      (node (ref "ULN5") (pin "10") (pinfunction "10_10") (pintype "bidirectional"))
    )
    (net (code "426") (name "unconnected-(ULN6-Pad10)") (class "Default")
      (node (ref "ULN6") (pin "10") (pinfunction "10_10") (pintype "bidirectional"))
    )
    (net (code "427") (name "unconnected-(ULN7-Pad10)") (class "Default")
      (node (ref "ULN7") (pin "10") (pinfunction "10_10") (pintype "bidirectional"))
    )
    (net (code "428") (name "unconnected-(ULN8-Pad10)") (class "Default")
      (node (ref "ULN8") (pin "10") (pinfunction "10_10") (pintype "bidirectional"))
    )
    (net (code "429") (name "unconnected-(ULN9-Pad10)") (class "Default")
      (node (ref "ULN9") (pin "10") (pinfunction "10_10") (pintype "bidirectional"))
    )
    (net (code "430") (name "unconnected-(ULN10-Pad10)") (class "Default")
      (node (ref "ULN10") (pin "10") (pinfunction "10_10") (pintype "bidirectional"))
    )
    (net (code "431") (name "unconnected-(ULN11-Pad10)") (class "Default")
      (node (ref "ULN11") (pin "10") (pinfunction "10_10") (pintype "bidirectional"))
    )
    (net (code "432") (name "unconnected-(ULN12-Pad10)") (class "Default")
      (node (ref "ULN12") (pin "10") (pinfunction "10_10") (pintype "bidirectional"))
    )
    (net (code "433") (name "unconnected-(ULN13-Pad10)") (class "Default")
      (node (ref "ULN13") (pin "10") (pinfunction "10_10") (pintype "bidirectional"))
    )
    (net (code "434") (name "unconnected-(ULN14-Pad10)") (class "Default")
      (node (ref "ULN14") (pin "10") (pinfunction "10_10") (pintype "bidirectional"))
    )
    (net (code "435") (name "unconnected-(ULN14-Pad11)") (class "Default")
      (node (ref "ULN14") (pin "11") (pinfunction "11_11") (pintype "bidirectional"))
    )
    (net (code "436") (name "unconnected-(ULN14-Pad12)") (class "Default")
      (node (ref "ULN14") (pin "12") (pinfunction "12_12") (pintype "bidirectional"))
    )
    (net (code "437") (name "unconnected-(ULN14-Pad13)") (class "Default")
      (node (ref "ULN14") (pin "13") (pinfunction "13_13") (pintype "bidirectional"))
    )
    (net (code "438") (name "unconnected-(ULN14-Pad14)") (class "Default")
      (node (ref "ULN14") (pin "14") (pinfunction "14_14") (pintype "bidirectional"))
    )
  )
)
